# SpeedOfLightController.net
KiCad netlist of a schematic drawn in EAGLE
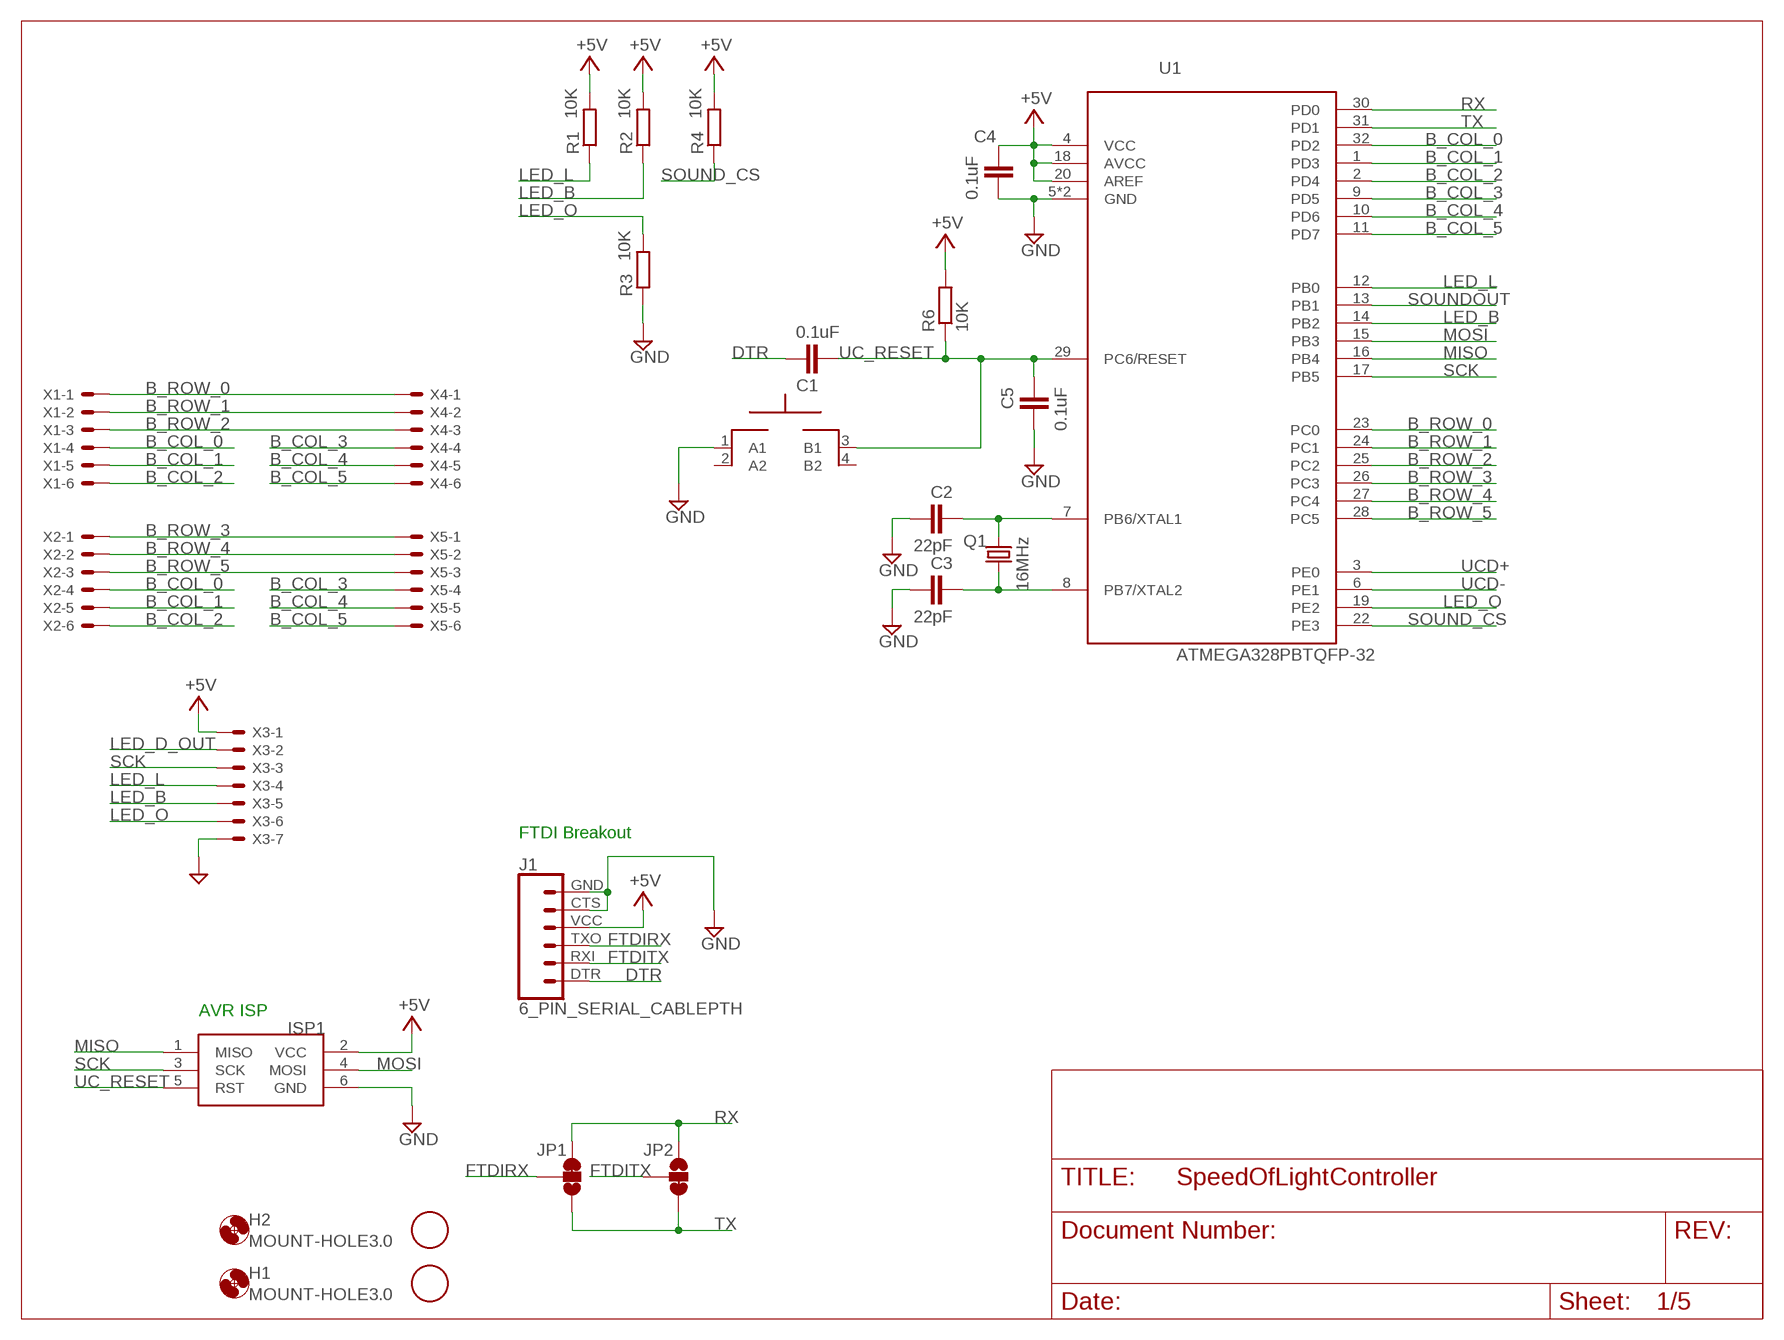
[diagram p0: schematic, sheet 1]
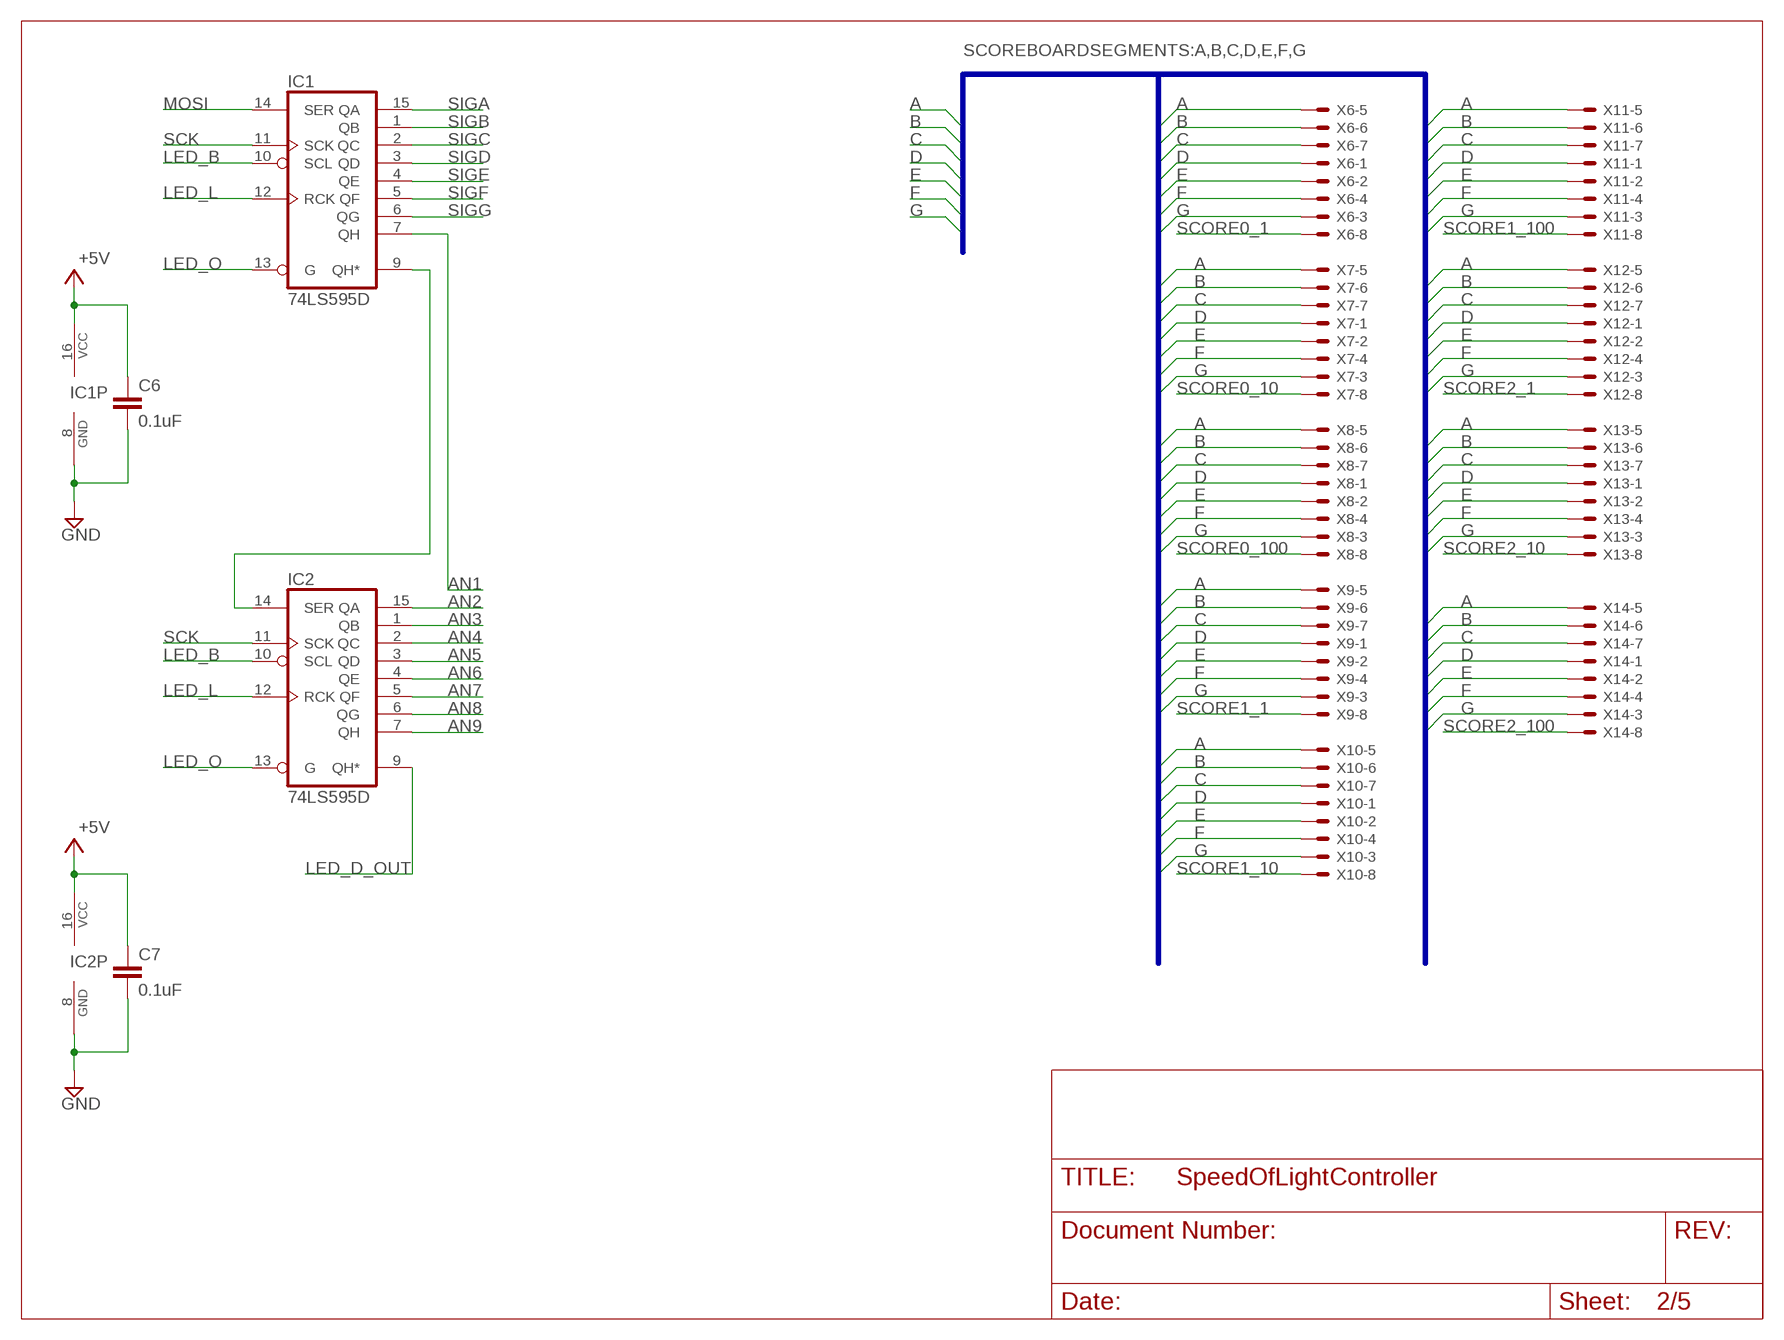
[diagram p1: schematic, sheet 2]
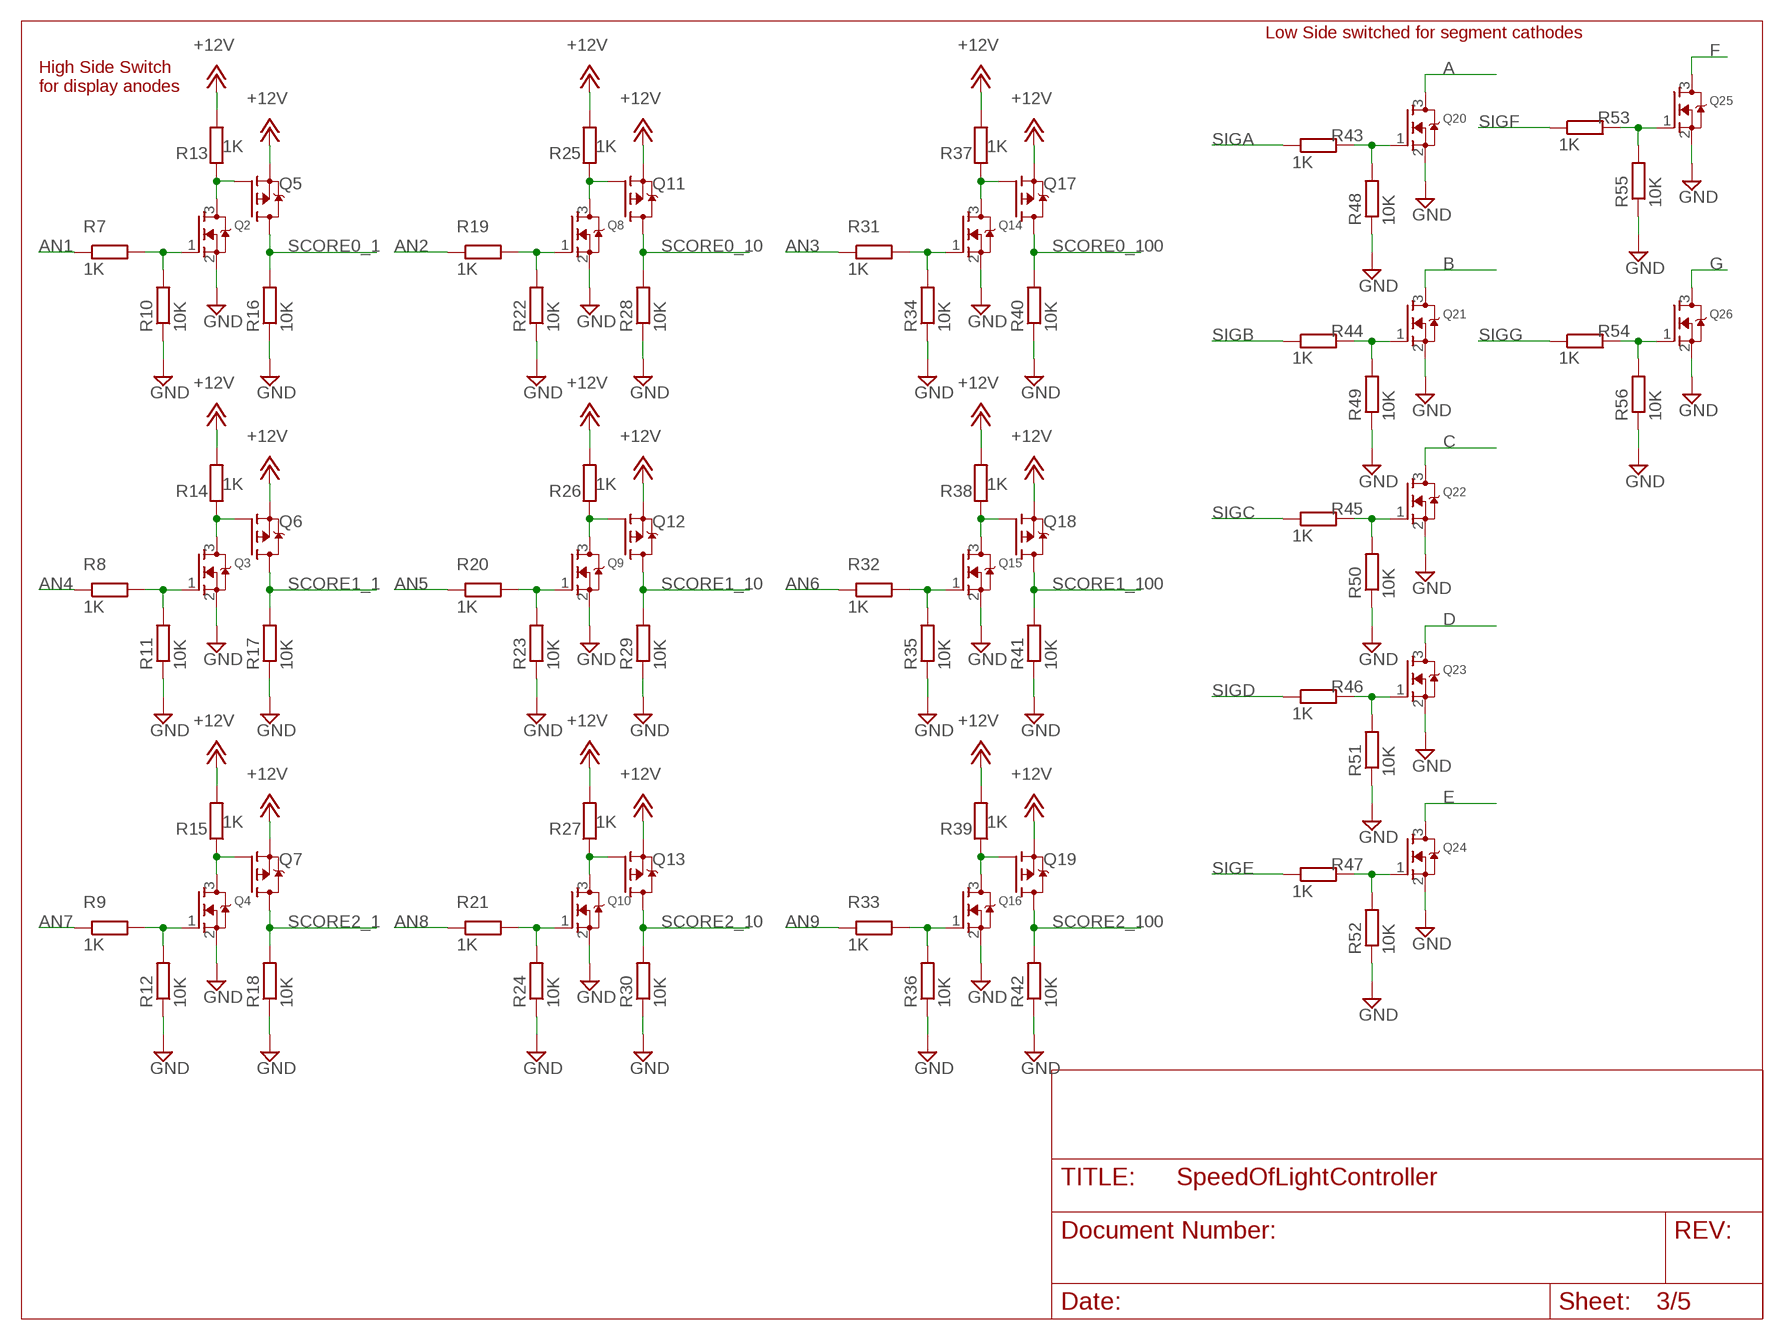
[diagram p2: schematic, sheet 3]
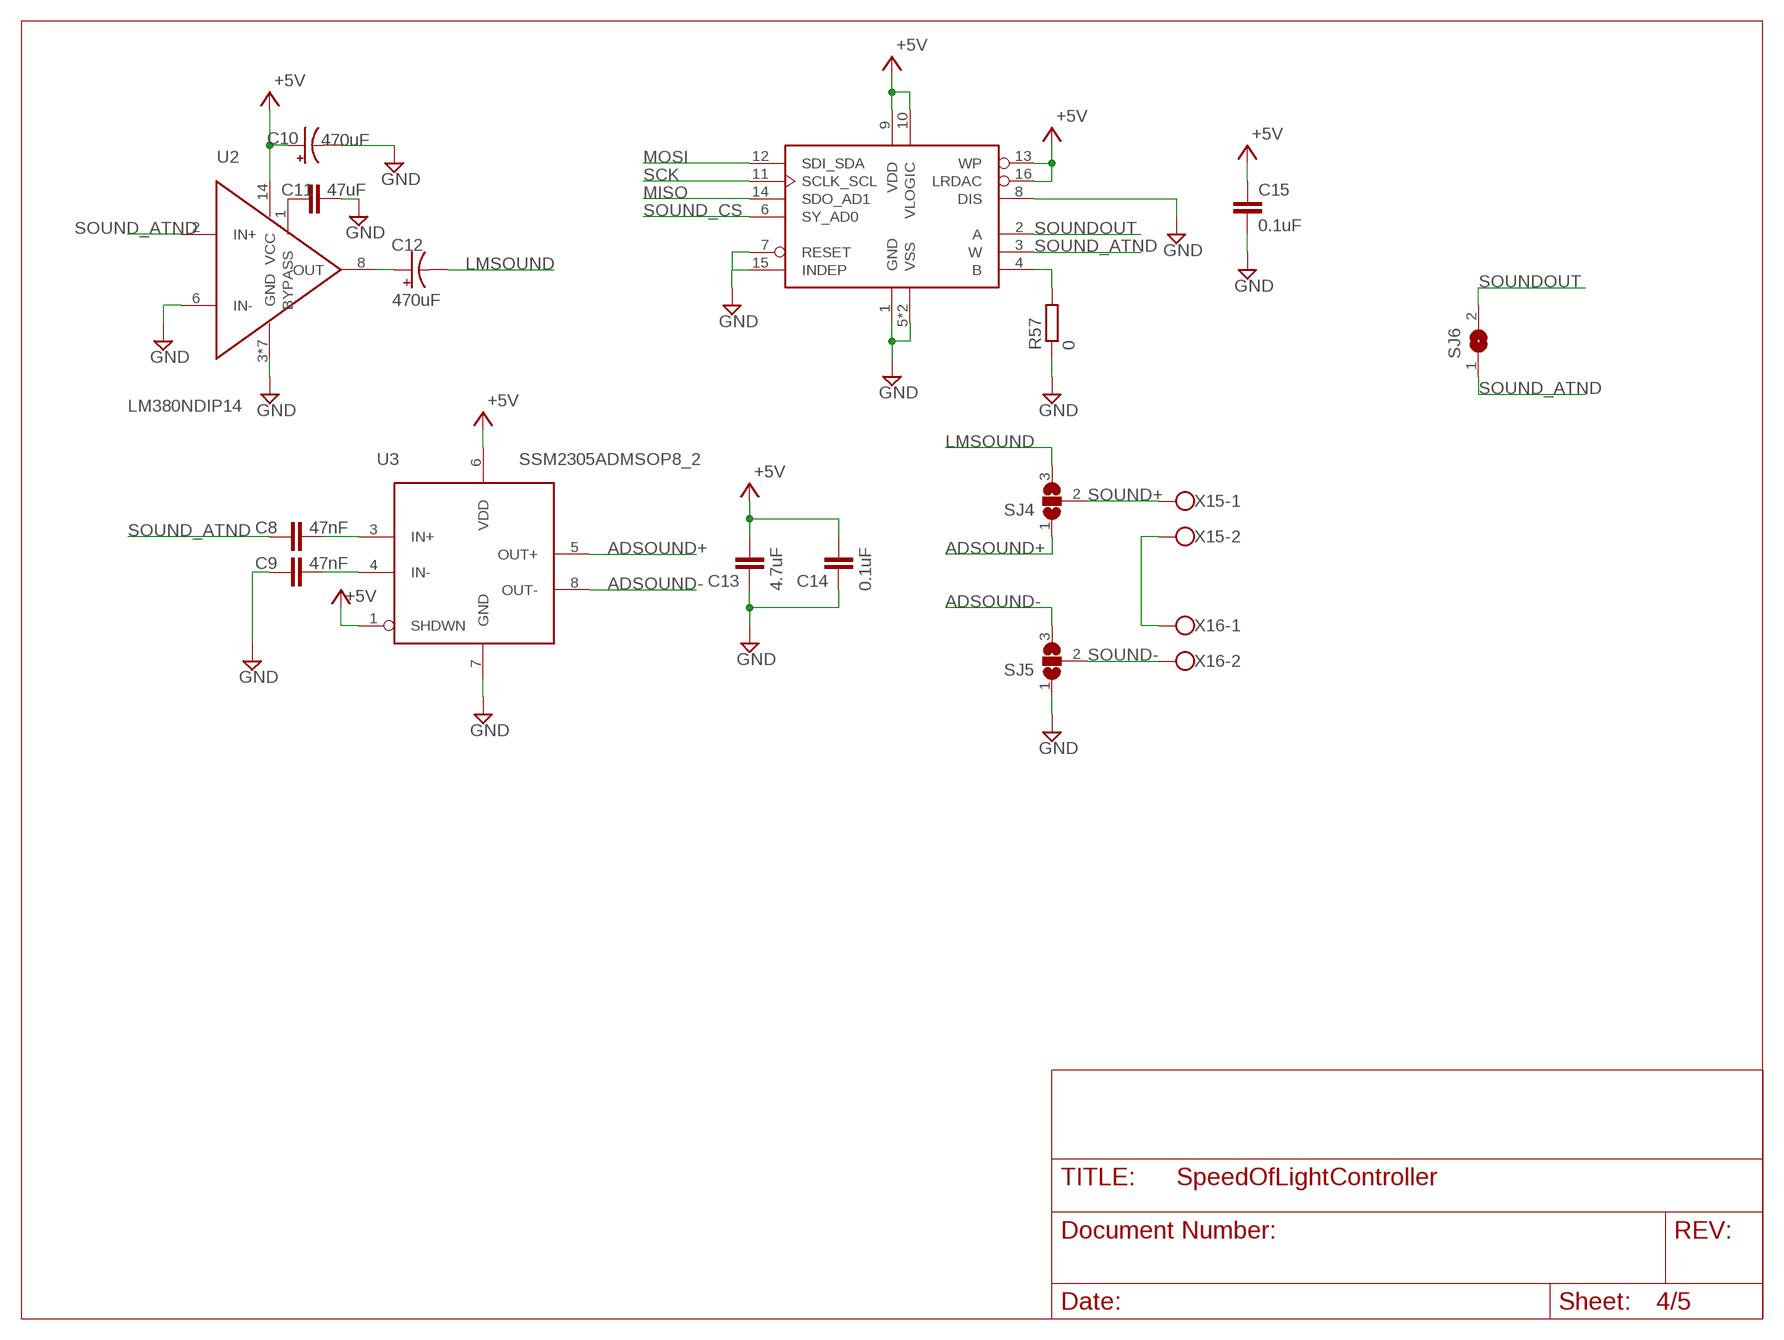
[diagram p3: schematic, sheet 4]
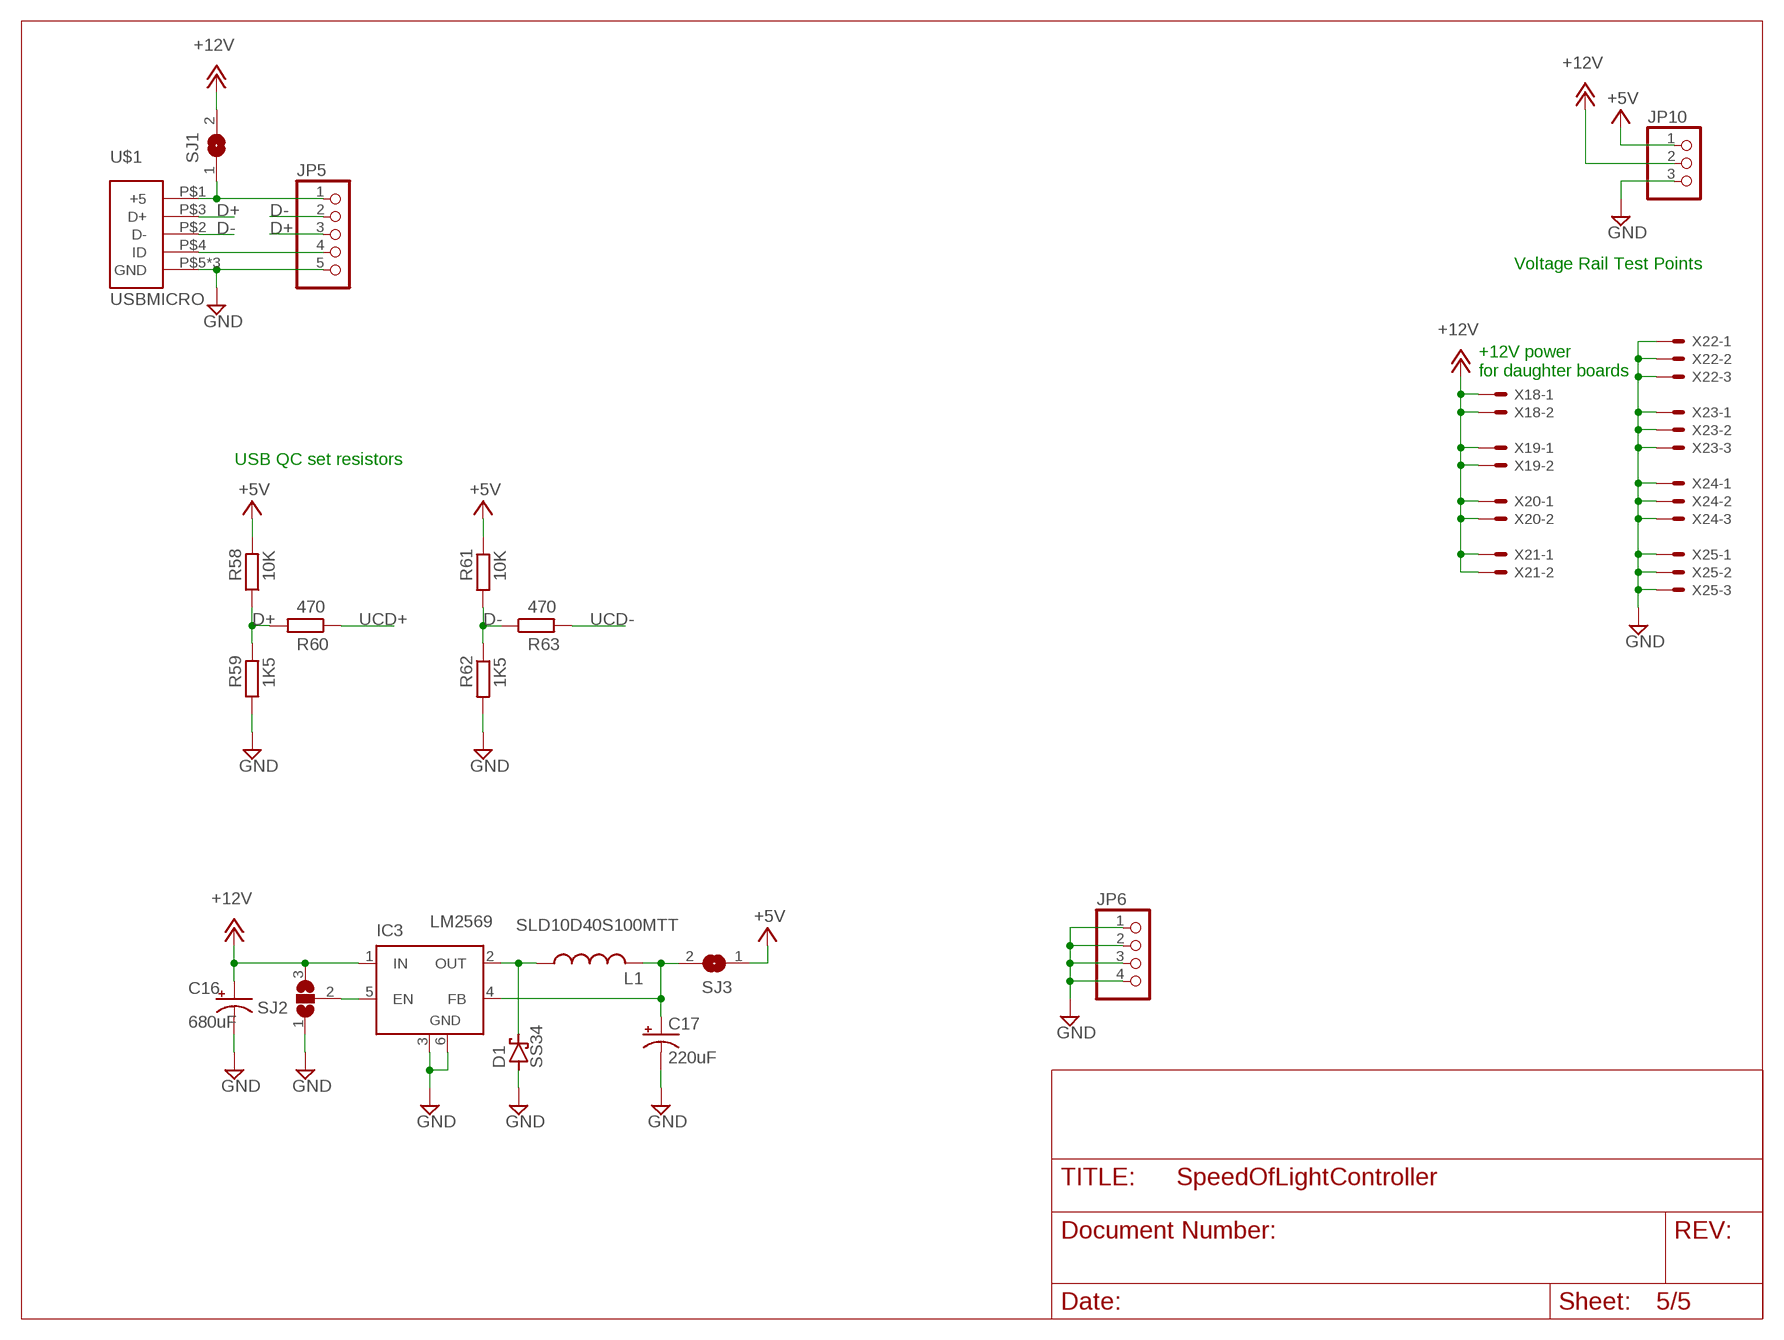
[diagram p4: schematic, sheet 5]

(export (version "E")
  (design (tool "Eeschema 10.0.6"))
  (components
    (comp (ref "C6")
      (value "0.1uF")
      (footprint "eagle-import:C0805")
      (libsource (lib "eagle-import") (part "C-EUC0805"))
    )
    (comp (ref "C7")
      (value "0.1uF")
      (footprint "eagle-import:C0805")
      (libsource (lib "eagle-import") (part "C-EUC0805"))
    )
    (comp (ref "IC1")
      (value "74LS595D")
      (footprint "eagle-import:SO16")
      (libsource (lib "eagle-import") (part "74595DLS"))
    )
    (comp (ref "IC2")
      (value "74LS595D")
      (footprint "eagle-import:SO16")
      (libsource (lib "eagle-import") (part "74595DLS"))
    )
    (comp (ref "X6")
      (value "JST-XH-08-PIN-LONG-PAD")
      (footprint "eagle-import:JST-XH-08-PACKAGE-LONG-PAD")
      (libsource (lib "eagle-import") (part "JST-XH-08-PIN-LONG-PAD"))
    )
    (comp (ref "X7")
      (value "JST-XH-08-PIN-LONG-PAD")
      (footprint "eagle-import:JST-XH-08-PACKAGE-LONG-PAD")
      (libsource (lib "eagle-import") (part "JST-XH-08-PIN-LONG-PAD"))
    )
    (comp (ref "X8")
      (value "JST-XH-08-PIN-LONG-PAD")
      (footprint "eagle-import:JST-XH-08-PACKAGE-LONG-PAD")
      (libsource (lib "eagle-import") (part "JST-XH-08-PIN-LONG-PAD"))
    )
    (comp (ref "X9")
      (value "JST-XH-08-PIN-LONG-PAD")
      (footprint "eagle-import:JST-XH-08-PACKAGE-LONG-PAD")
      (libsource (lib "eagle-import") (part "JST-XH-08-PIN-LONG-PAD"))
    )
    (comp (ref "X10")
      (value "JST-XH-08-PIN-LONG-PAD")
      (footprint "eagle-import:JST-XH-08-PACKAGE-LONG-PAD")
      (libsource (lib "eagle-import") (part "JST-XH-08-PIN-LONG-PAD"))
    )
    (comp (ref "X11")
      (value "JST-XH-08-PIN-LONG-PAD")
      (footprint "eagle-import:JST-XH-08-PACKAGE-LONG-PAD")
      (libsource (lib "eagle-import") (part "JST-XH-08-PIN-LONG-PAD"))
    )
    (comp (ref "X12")
      (value "JST-XH-08-PIN-LONG-PAD")
      (footprint "eagle-import:JST-XH-08-PACKAGE-LONG-PAD")
      (libsource (lib "eagle-import") (part "JST-XH-08-PIN-LONG-PAD"))
    )
    (comp (ref "X13")
      (value "JST-XH-08-PIN-LONG-PAD")
      (footprint "eagle-import:JST-XH-08-PACKAGE-LONG-PAD")
      (libsource (lib "eagle-import") (part "JST-XH-08-PIN-LONG-PAD"))
    )
    (comp (ref "X14")
      (value "JST-XH-08-PIN-LONG-PAD")
      (footprint "eagle-import:JST-XH-08-PACKAGE-LONG-PAD")
      (libsource (lib "eagle-import") (part "JST-XH-08-PIN-LONG-PAD"))
    )
    (comp (ref "C16")
      (value "680uF")
      (footprint "eagle-import:140CLH-0810")
      (libsource (lib "eagle-import") (part "CPOL-US140CLH-0810"))
    )
    (comp (ref "C17")
      (value "220uF")
      (footprint "eagle-import:140CLH-0810")
      (libsource (lib "eagle-import") (part "CPOL-US140CLH-0810"))
    )
    (comp (ref "D1")
      (value "SS34")
      (footprint "eagle-import:SMA")
      (libsource (lib "eagle-import") (part "SS34"))
    )
    (comp (ref "IC3")
      (value "LM2596S")
      (footprint "eagle-import:TO263-5")
      (libsource (lib "eagle-import") (part "LM2596S"))
    )
    (comp (ref "JP5")
      (value "PINHD-1X5")
      (footprint "eagle-import:1X05")
      (libsource (lib "eagle-import") (part "PINHD-1X5"))
    )
    (comp (ref "JP6")
      (value "PINHD-1X4")
      (footprint "eagle-import:1X04")
      (libsource (lib "eagle-import") (part "PINHD-1X4"))
    )
    (comp (ref "JP10")
      (value "PINHD-1X3")
      (footprint "eagle-import:1X03")
      (libsource (lib "eagle-import") (part "PINHD-1X3"))
    )
    (comp (ref "L1")
      (value "SLD10D40S100MTT")
      (footprint "eagle-import:SMD10.5X10.3")
      (libsource (lib "eagle-import") (part "SLD10D40S100MTT"))
    )
    (comp (ref "R58")
      (value "10K")
      (footprint "eagle-import:R0805")
      (libsource (lib "eagle-import") (part "R-EU_R0805"))
    )
    (comp (ref "R59")
      (value "1K5")
      (footprint "eagle-import:R0805")
      (libsource (lib "eagle-import") (part "R-EU_R0805"))
    )
    (comp (ref "R60")
      (value "470")
      (footprint "eagle-import:R0805")
      (libsource (lib "eagle-import") (part "R-EU_R0805"))
    )
    (comp (ref "R61")
      (value "10K")
      (footprint "eagle-import:R0805")
      (libsource (lib "eagle-import") (part "R-EU_R0805"))
    )
    (comp (ref "R62")
      (value "1K5")
      (footprint "eagle-import:R0805")
      (libsource (lib "eagle-import") (part "R-EU_R0805"))
    )
    (comp (ref "R63")
      (value "470")
      (footprint "eagle-import:R0805")
      (libsource (lib "eagle-import") (part "R-EU_R0805"))
    )
    (comp (ref "SJ1") (value "SJ") (footprint "eagle-import:SJ") (libsource (lib "eagle-import") (part "SJ")))
    (comp (ref "SJ2")
      (value "SJ2WW")
      (footprint "eagle-import:SJ_2W")
      (libsource (lib "eagle-import") (part "SJ2WW"))
    )
    (comp (ref "SJ3") (value "SJ") (footprint "eagle-import:SJ") (libsource (lib "eagle-import") (part "SJ")))
    (comp (ref "U$1")
      (value "USBMICRO")
      (footprint "eagle-import:USBMICRO")
      (libsource (lib "eagle-import") (part "USBMICRO"))
    )
    (comp (ref "X18")
      (value "JST-XH-02-PIN-LONG-PAD")
      (footprint "eagle-import:JST-XH-02-PACKAGE-LONG-PAD")
      (libsource (lib "eagle-import") (part "JST-XH-02-PIN-LONG-PAD"))
    )
    (comp (ref "X19")
      (value "JST-XH-02-PIN-LONG-PAD")
      (footprint "eagle-import:JST-XH-02-PACKAGE-LONG-PAD")
      (libsource (lib "eagle-import") (part "JST-XH-02-PIN-LONG-PAD"))
    )
    (comp (ref "X20")
      (value "JST-XH-02-PIN-LONG-PAD")
      (footprint "eagle-import:JST-XH-02-PACKAGE-LONG-PAD")
      (libsource (lib "eagle-import") (part "JST-XH-02-PIN-LONG-PAD"))
    )
    (comp (ref "X21")
      (value "JST-XH-02-PIN-LONG-PAD")
      (footprint "eagle-import:JST-XH-02-PACKAGE-LONG-PAD")
      (libsource (lib "eagle-import") (part "JST-XH-02-PIN-LONG-PAD"))
    )
    (comp (ref "X22")
      (value "JST-XH-03-PIN-LONG-PAD")
      (footprint "eagle-import:JST-XH-03-PACKAGE-LONG-PAD")
      (libsource (lib "eagle-import") (part "JST-XH-03-PIN-LONG-PAD"))
    )
    (comp (ref "X23")
      (value "JST-XH-03-PIN-LONG-PAD")
      (footprint "eagle-import:JST-XH-03-PACKAGE-LONG-PAD")
      (libsource (lib "eagle-import") (part "JST-XH-03-PIN-LONG-PAD"))
    )
    (comp (ref "X24")
      (value "JST-XH-03-PIN-LONG-PAD")
      (footprint "eagle-import:JST-XH-03-PACKAGE-LONG-PAD")
      (libsource (lib "eagle-import") (part "JST-XH-03-PIN-LONG-PAD"))
    )
    (comp (ref "X25")
      (value "JST-XH-03-PIN-LONG-PAD")
      (footprint "eagle-import:JST-XH-03-PACKAGE-LONG-PAD")
      (libsource (lib "eagle-import") (part "JST-XH-03-PIN-LONG-PAD"))
    )
    (comp (ref "C1")
      (value "0.1uF")
      (footprint "eagle-import:C0805")
      (libsource (lib "eagle-import") (part "C-EUC0805"))
    )
    (comp (ref "C2")
      (value "22pF")
      (footprint "eagle-import:C0805")
      (libsource (lib "eagle-import") (part "C-EUC0805"))
    )
    (comp (ref "C3")
      (value "22pF")
      (footprint "eagle-import:C0805")
      (libsource (lib "eagle-import") (part "C-EUC0805"))
    )
    (comp (ref "C4")
      (value "0.1uF")
      (footprint "eagle-import:C0805")
      (libsource (lib "eagle-import") (part "C-EUC0805"))
    )
    (comp (ref "C5")
      (value "0.1uF")
      (footprint "eagle-import:C0805")
      (libsource (lib "eagle-import") (part "C-EUC0805"))
    )
    (comp (ref "F1")
      (value "FIDUCIAL")
      (footprint "eagle-import:FIDUCIAL_1MM")
      (libsource (lib "eagle-import") (part "FIDUCIAL"))
    )
    (comp (ref "F2")
      (value "FIDUCIAL")
      (footprint "eagle-import:FIDUCIAL_1MM")
      (libsource (lib "eagle-import") (part "FIDUCIAL"))
    )
    (comp (ref "H1")
      (value "MOUNT-HOLE3.0")
      (footprint "eagle-import:3,0")
      (libsource (lib "eagle-import") (part "MOUNT-HOLE3.0"))
    )
    (comp (ref "H2")
      (value "MOUNT-HOLE3.0")
      (footprint "eagle-import:3,0")
      (libsource (lib "eagle-import") (part "MOUNT-HOLE3.0"))
    )
    (comp (ref "ISP1")
      (value "AVRISP-6")
      (footprint "eagle-import:AVRISP")
      (libsource (lib "eagle-import") (part "AVRISP-6"))
    )
    (comp (ref "J1")
      (value "6_PIN_SERIAL_CABLEPTH")
      (footprint "eagle-import:FTDI_BASIC")
      (libsource (lib "eagle-import") (part "6_PIN_SERIAL_CABLEPTH"))
    )
    (comp (ref "JP1")
      (value "JUMPER-SMT_3_1-NC_TRACE_SILK")
      (footprint "eagle-import:SMT-JUMPER_3_1-NC_TRACE_SILK")
      (libsource (lib "eagle-import") (part "JUMPER-SMT_3_1-NC_TRACE_SILK"))
    )
    (comp (ref "JP2")
      (value "JUMPER-SMT_3_1-NC_TRACE_SILK")
      (footprint "eagle-import:SMT-JUMPER_3_1-NC_TRACE_SILK")
      (libsource (lib "eagle-import") (part "JUMPER-SMT_3_1-NC_TRACE_SILK"))
    )
    (comp (ref "Q1")
      (value "16MHz")
      (footprint "eagle-import:HC49UP")
      (libsource (lib "eagle-import") (part "CRYSTALHC49UP"))
    )
    (comp (ref "R1")
      (value "10K")
      (footprint "eagle-import:R0805")
      (libsource (lib "eagle-import") (part "R-EU_R0805"))
    )
    (comp (ref "R2")
      (value "10K")
      (footprint "eagle-import:R0805")
      (libsource (lib "eagle-import") (part "R-EU_R0805"))
    )
    (comp (ref "R3")
      (value "10K")
      (footprint "eagle-import:R0805")
      (libsource (lib "eagle-import") (part "R-EU_R0805"))
    )
    (comp (ref "R4")
      (value "10K")
      (footprint "eagle-import:R0805")
      (libsource (lib "eagle-import") (part "R-EU_R0805"))
    )
    (comp (ref "R6")
      (value "10K")
      (footprint "eagle-import:R0805")
      (libsource (lib "eagle-import") (part "R-EU_R0805"))
    )
    (comp (ref "SW1")
      (value "MOMENTARYBUTTON")
      (footprint "eagle-import:SPST_NO_SMD")
      (libsource (lib "eagle-import") (part "MOMENTARYBUTTON"))
    )
    (comp (ref "U1")
      (value "ATMEGA328PBTQFP-32")
      (footprint "eagle-import:QFP80P900X900X120-32N")
      (libsource (lib "eagle-import") (part "ATMEGA328PBTQFP-32"))
    )
    (comp (ref "X1")
      (value "JST-XH-06-PIN-LONG-PAD")
      (footprint "eagle-import:JST-XH-06-PACKAGE-LONG-PAD")
      (libsource (lib "eagle-import") (part "JST-XH-06-PIN-LONG-PAD"))
    )
    (comp (ref "X2")
      (value "JST-XH-06-PIN-LONG-PAD")
      (footprint "eagle-import:JST-XH-06-PACKAGE-LONG-PAD")
      (libsource (lib "eagle-import") (part "JST-XH-06-PIN-LONG-PAD"))
    )
    (comp (ref "X3")
      (value "JST-XH-07-PIN-LONG-PAD")
      (footprint "eagle-import:JST-XH-07-PACKAGE-LONG-PAD")
      (libsource (lib "eagle-import") (part "JST-XH-07-PIN-LONG-PAD"))
    )
    (comp (ref "X4")
      (value "JST-XH-06-PIN-LONG-PAD")
      (footprint "eagle-import:JST-XH-06-PACKAGE-LONG-PAD")
      (libsource (lib "eagle-import") (part "JST-XH-06-PIN-LONG-PAD"))
    )
    (comp (ref "X5")
      (value "JST-XH-06-PIN-LONG-PAD")
      (footprint "eagle-import:JST-XH-06-PACKAGE-LONG-PAD")
      (libsource (lib "eagle-import") (part "JST-XH-06-PIN-LONG-PAD"))
    )
    (comp (ref "C8")
      (value "47nF")
      (footprint "eagle-import:C0805")
      (libsource (lib "eagle-import") (part "C-EUC0805"))
    )
    (comp (ref "C9")
      (value "47nF")
      (footprint "eagle-import:C0805")
      (libsource (lib "eagle-import") (part "C-EUC0805"))
    )
    (comp (ref "C10")
      (value "470uF")
      (footprint "eagle-import:140CLH-0810")
      (libsource (lib "eagle-import") (part "CPOL-US140CLH-0810"))
    )
    (comp (ref "C11")
      (value "47uF")
      (footprint "eagle-import:C0805")
      (libsource (lib "eagle-import") (part "C-EUC0805"))
    )
    (comp (ref "C12")
      (value "470uF")
      (footprint "eagle-import:140CLH-0810")
      (libsource (lib "eagle-import") (part "CPOL-US140CLH-0810"))
    )
    (comp (ref "C13")
      (value "4.7uF")
      (footprint "eagle-import:C0805")
      (libsource (lib "eagle-import") (part "C-EUC0805"))
    )
    (comp (ref "C14")
      (value "0.1uF")
      (footprint "eagle-import:C0805")
      (libsource (lib "eagle-import") (part "C-EUC0805"))
    )
    (comp (ref "C15")
      (value "0.1uF")
      (footprint "eagle-import:C0805")
      (libsource (lib "eagle-import") (part "C-EUC0805"))
    )
    (comp (ref "R57")
      (value "0")
      (footprint "eagle-import:R0805W")
      (libsource (lib "eagle-import") (part "R-EU_R0805W"))
    )
    (comp (ref "SJ4")
      (value "SJ2WW")
      (footprint "eagle-import:SJ_2W")
      (libsource (lib "eagle-import") (part "SJ2WW"))
    )
    (comp (ref "SJ5")
      (value "SJ2WW")
      (footprint "eagle-import:SJ_2W")
      (libsource (lib "eagle-import") (part "SJ2WW"))
    )
    (comp (ref "SJ6") (value "SJ") (footprint "eagle-import:SJ") (libsource (lib "eagle-import") (part "SJ")))
    (comp (ref "U2")
      (value "LM380NDIP14")
      (footprint "eagle-import:DIP762W53P254L1969H508Q14B")
      (libsource (lib "eagle-import") (part "LM380NDIP14"))
    )
    (comp (ref "U3")
      (value "SSM2305ADMSOP8_2")
      (footprint "eagle-import:SOP65P490X95-8N")
      (libsource (lib "eagle-import") (part "SSM2305ADMSOP8_2"))
    )
    (comp (ref "U4")
      (value "AD5141ADLFCSP3")
      (footprint "eagle-import:QFN50P300X300X80-17T160N")
      (libsource (lib "eagle-import") (part "AD5141ADLFCSP3"))
    )
    (comp (ref "X15")
      (value "1X02_5MM_SCREW")
      (footprint "eagle-import:W237-102")
      (fields (field (name "MPN") "237-102"))
      (libsource (lib "eagle-import") (part "1X02_5MM_SCREW"))
    )
    (comp (ref "X16")
      (value "1X02_5MM_SCREW")
      (footprint "eagle-import:W237-102")
      (fields (field (name "MPN") "237-102"))
      (libsource (lib "eagle-import") (part "1X02_5MM_SCREW"))
    )
    (comp (ref "Q2")
      (value "AO3414SOT23")
      (footprint "eagle-import:SOT95P240X110-3N")
      (libsource (lib "eagle-import") (part "AO3414SOT23"))
    )
    (comp (ref "Q3")
      (value "AO3414SOT23")
      (footprint "eagle-import:SOT95P240X110-3N")
      (libsource (lib "eagle-import") (part "AO3414SOT23"))
    )
    (comp (ref "Q4")
      (value "AO3414SOT23")
      (footprint "eagle-import:SOT95P240X110-3N")
      (libsource (lib "eagle-import") (part "AO3414SOT23"))
    )
    (comp (ref "Q5")
      (value "AO3415")
      (footprint "eagle-import:SOT95P240X110-3N")
      (libsource (lib "eagle-import") (part "AO3415"))
    )
    (comp (ref "Q6")
      (value "AO3415")
      (footprint "eagle-import:SOT95P240X110-3N")
      (libsource (lib "eagle-import") (part "AO3415"))
    )
    (comp (ref "Q7")
      (value "AO3415")
      (footprint "eagle-import:SOT95P240X110-3N")
      (libsource (lib "eagle-import") (part "AO3415"))
    )
    (comp (ref "Q8")
      (value "AO3414SOT23")
      (footprint "eagle-import:SOT95P240X110-3N")
      (libsource (lib "eagle-import") (part "AO3414SOT23"))
    )
    (comp (ref "Q9")
      (value "AO3414SOT23")
      (footprint "eagle-import:SOT95P240X110-3N")
      (libsource (lib "eagle-import") (part "AO3414SOT23"))
    )
    (comp (ref "Q10")
      (value "AO3414SOT23")
      (footprint "eagle-import:SOT95P240X110-3N")
      (libsource (lib "eagle-import") (part "AO3414SOT23"))
    )
    (comp (ref "Q11")
      (value "AO3415")
      (footprint "eagle-import:SOT95P240X110-3N")
      (libsource (lib "eagle-import") (part "AO3415"))
    )
    (comp (ref "Q12")
      (value "AO3415")
      (footprint "eagle-import:SOT95P240X110-3N")
      (libsource (lib "eagle-import") (part "AO3415"))
    )
    (comp (ref "Q13")
      (value "AO3415")
      (footprint "eagle-import:SOT95P240X110-3N")
      (libsource (lib "eagle-import") (part "AO3415"))
    )
    (comp (ref "Q14")
      (value "AO3414SOT23")
      (footprint "eagle-import:SOT95P240X110-3N")
      (libsource (lib "eagle-import") (part "AO3414SOT23"))
    )
    (comp (ref "Q15")
      (value "AO3414SOT23")
      (footprint "eagle-import:SOT95P240X110-3N")
      (libsource (lib "eagle-import") (part "AO3414SOT23"))
    )
    (comp (ref "Q16")
      (value "AO3414SOT23")
      (footprint "eagle-import:SOT95P240X110-3N")
      (libsource (lib "eagle-import") (part "AO3414SOT23"))
    )
    (comp (ref "Q17")
      (value "AO3415")
      (footprint "eagle-import:SOT95P240X110-3N")
      (libsource (lib "eagle-import") (part "AO3415"))
    )
    (comp (ref "Q18")
      (value "AO3415")
      (footprint "eagle-import:SOT95P240X110-3N")
      (libsource (lib "eagle-import") (part "AO3415"))
    )
    (comp (ref "Q19")
      (value "AO3415")
      (footprint "eagle-import:SOT95P240X110-3N")
      (libsource (lib "eagle-import") (part "AO3415"))
    )
    (comp (ref "Q20")
      (value "AO3414SOT23")
      (footprint "eagle-import:SOT95P240X110-3N")
      (libsource (lib "eagle-import") (part "AO3414SOT23"))
    )
    (comp (ref "Q21")
      (value "AO3414SOT23")
      (footprint "eagle-import:SOT95P240X110-3N")
      (libsource (lib "eagle-import") (part "AO3414SOT23"))
    )
    (comp (ref "Q22")
      (value "AO3414SOT23")
      (footprint "eagle-import:SOT95P240X110-3N")
      (libsource (lib "eagle-import") (part "AO3414SOT23"))
    )
    (comp (ref "Q23")
      (value "AO3414SOT23")
      (footprint "eagle-import:SOT95P240X110-3N")
      (libsource (lib "eagle-import") (part "AO3414SOT23"))
    )
    (comp (ref "Q24")
      (value "AO3414SOT23")
      (footprint "eagle-import:SOT95P240X110-3N")
      (libsource (lib "eagle-import") (part "AO3414SOT23"))
    )
    (comp (ref "Q25")
      (value "AO3414SOT23")
      (footprint "eagle-import:SOT95P240X110-3N")
      (libsource (lib "eagle-import") (part "AO3414SOT23"))
    )
    (comp (ref "Q26")
      (value "AO3414SOT23")
      (footprint "eagle-import:SOT95P240X110-3N")
      (libsource (lib "eagle-import") (part "AO3414SOT23"))
    )
    (comp (ref "R7")
      (value "1K")
      (footprint "eagle-import:R0805")
      (libsource (lib "eagle-import") (part "R-EU_R0805"))
    )
    (comp (ref "R8")
      (value "1K")
      (footprint "eagle-import:R0805")
      (libsource (lib "eagle-import") (part "R-EU_R0805"))
    )
    (comp (ref "R9")
      (value "1K")
      (footprint "eagle-import:R0805")
      (libsource (lib "eagle-import") (part "R-EU_R0805"))
    )
    (comp (ref "R10")
      (value "10K")
      (footprint "eagle-import:R0805")
      (libsource (lib "eagle-import") (part "R-EU_R0805"))
    )
    (comp (ref "R11")
      (value "10K")
      (footprint "eagle-import:R0805")
      (libsource (lib "eagle-import") (part "R-EU_R0805"))
    )
    (comp (ref "R12")
      (value "10K")
      (footprint "eagle-import:R0805")
      (libsource (lib "eagle-import") (part "R-EU_R0805"))
    )
    (comp (ref "R13")
      (value "1K")
      (footprint "eagle-import:R0805")
      (libsource (lib "eagle-import") (part "R-EU_R0805"))
    )
    (comp (ref "R14")
      (value "1K")
      (footprint "eagle-import:R0805")
      (libsource (lib "eagle-import") (part "R-EU_R0805"))
    )
    (comp (ref "R15")
      (value "1K")
      (footprint "eagle-import:R0805")
      (libsource (lib "eagle-import") (part "R-EU_R0805"))
    )
    (comp (ref "R16")
      (value "10K")
      (footprint "eagle-import:R0805")
      (libsource (lib "eagle-import") (part "R-EU_R0805"))
    )
    (comp (ref "R17")
      (value "10K")
      (footprint "eagle-import:R0805")
      (libsource (lib "eagle-import") (part "R-EU_R0805"))
    )
    (comp (ref "R18")
      (value "10K")
      (footprint "eagle-import:R0805")
      (libsource (lib "eagle-import") (part "R-EU_R0805"))
    )
    (comp (ref "R19")
      (value "1K")
      (footprint "eagle-import:R0805")
      (libsource (lib "eagle-import") (part "R-EU_R0805"))
    )
    (comp (ref "R20")
      (value "1K")
      (footprint "eagle-import:R0805")
      (libsource (lib "eagle-import") (part "R-EU_R0805"))
    )
    (comp (ref "R21")
      (value "1K")
      (footprint "eagle-import:R0805")
      (libsource (lib "eagle-import") (part "R-EU_R0805"))
    )
    (comp (ref "R22")
      (value "10K")
      (footprint "eagle-import:R0805")
      (libsource (lib "eagle-import") (part "R-EU_R0805"))
    )
    (comp (ref "R23")
      (value "10K")
      (footprint "eagle-import:R0805")
      (libsource (lib "eagle-import") (part "R-EU_R0805"))
    )
    (comp (ref "R24")
      (value "10K")
      (footprint "eagle-import:R0805")
      (libsource (lib "eagle-import") (part "R-EU_R0805"))
    )
    (comp (ref "R25")
      (value "1K")
      (footprint "eagle-import:R0805")
      (libsource (lib "eagle-import") (part "R-EU_R0805"))
    )
    (comp (ref "R26")
      (value "1K")
      (footprint "eagle-import:R0805")
      (libsource (lib "eagle-import") (part "R-EU_R0805"))
    )
    (comp (ref "R27")
      (value "1K")
      (footprint "eagle-import:R0805")
      (libsource (lib "eagle-import") (part "R-EU_R0805"))
    )
    (comp (ref "R28")
      (value "10K")
      (footprint "eagle-import:R0805")
      (libsource (lib "eagle-import") (part "R-EU_R0805"))
    )
    (comp (ref "R29")
      (value "10K")
      (footprint "eagle-import:R0805")
      (libsource (lib "eagle-import") (part "R-EU_R0805"))
    )
    (comp (ref "R30")
      (value "10K")
      (footprint "eagle-import:R0805")
      (libsource (lib "eagle-import") (part "R-EU_R0805"))
    )
    (comp (ref "R31")
      (value "1K")
      (footprint "eagle-import:R0805")
      (libsource (lib "eagle-import") (part "R-EU_R0805"))
    )
    (comp (ref "R32")
      (value "1K")
      (footprint "eagle-import:R0805")
      (libsource (lib "eagle-import") (part "R-EU_R0805"))
    )
    (comp (ref "R33")
      (value "1K")
      (footprint "eagle-import:R0805")
      (libsource (lib "eagle-import") (part "R-EU_R0805"))
    )
    (comp (ref "R34")
      (value "10K")
      (footprint "eagle-import:R0805")
      (libsource (lib "eagle-import") (part "R-EU_R0805"))
    )
    (comp (ref "R35")
      (value "10K")
      (footprint "eagle-import:R0805")
      (libsource (lib "eagle-import") (part "R-EU_R0805"))
    )
    (comp (ref "R36")
      (value "10K")
      (footprint "eagle-import:R0805")
      (libsource (lib "eagle-import") (part "R-EU_R0805"))
    )
    (comp (ref "R37")
      (value "1K")
      (footprint "eagle-import:R0805")
      (libsource (lib "eagle-import") (part "R-EU_R0805"))
    )
    (comp (ref "R38")
      (value "1K")
      (footprint "eagle-import:R0805")
      (libsource (lib "eagle-import") (part "R-EU_R0805"))
    )
    (comp (ref "R39")
      (value "1K")
      (footprint "eagle-import:R0805")
      (libsource (lib "eagle-import") (part "R-EU_R0805"))
    )
    (comp (ref "R40")
      (value "10K")
      (footprint "eagle-import:R0805")
      (libsource (lib "eagle-import") (part "R-EU_R0805"))
    )
    (comp (ref "R41")
      (value "10K")
      (footprint "eagle-import:R0805")
      (libsource (lib "eagle-import") (part "R-EU_R0805"))
    )
    (comp (ref "R42")
      (value "10K")
      (footprint "eagle-import:R0805")
      (libsource (lib "eagle-import") (part "R-EU_R0805"))
    )
    (comp (ref "R43")
      (value "1K")
      (footprint "eagle-import:R0805")
      (libsource (lib "eagle-import") (part "R-EU_R0805"))
    )
    (comp (ref "R44")
      (value "1K")
      (footprint "eagle-import:R0805")
      (libsource (lib "eagle-import") (part "R-EU_R0805"))
    )
    (comp (ref "R45")
      (value "1K")
      (footprint "eagle-import:R0805")
      (libsource (lib "eagle-import") (part "R-EU_R0805"))
    )
    (comp (ref "R46")
      (value "1K")
      (footprint "eagle-import:R0805")
      (libsource (lib "eagle-import") (part "R-EU_R0805"))
    )
    (comp (ref "R47")
      (value "1K")
      (footprint "eagle-import:R0805")
      (libsource (lib "eagle-import") (part "R-EU_R0805"))
    )
    (comp (ref "R48")
      (value "10K")
      (footprint "eagle-import:R0805")
      (libsource (lib "eagle-import") (part "R-EU_R0805"))
    )
    (comp (ref "R49")
      (value "10K")
      (footprint "eagle-import:R0805")
      (libsource (lib "eagle-import") (part "R-EU_R0805"))
    )
    (comp (ref "R50")
      (value "10K")
      (footprint "eagle-import:R0805")
      (libsource (lib "eagle-import") (part "R-EU_R0805"))
    )
    (comp (ref "R51")
      (value "10K")
      (footprint "eagle-import:R0805")
      (libsource (lib "eagle-import") (part "R-EU_R0805"))
    )
    (comp (ref "R52")
      (value "10K")
      (footprint "eagle-import:R0805")
      (libsource (lib "eagle-import") (part "R-EU_R0805"))
    )
    (comp (ref "R53")
      (value "1K")
      (footprint "eagle-import:R0805")
      (libsource (lib "eagle-import") (part "R-EU_R0805"))
    )
    (comp (ref "R54")
      (value "1K")
      (footprint "eagle-import:R0805")
      (libsource (lib "eagle-import") (part "R-EU_R0805"))
    )
    (comp (ref "R55")
      (value "10K")
      (footprint "eagle-import:R0805")
      (libsource (lib "eagle-import") (part "R-EU_R0805"))
    )
    (comp (ref "R56")
      (value "10K")
      (footprint "eagle-import:R0805")
      (libsource (lib "eagle-import") (part "R-EU_R0805"))
    )
  )
  (nets
    (net (code "2") (name "+5V") (class "Default")
      (node (ref "C10") (pin "+") (pinfunction "+_+") (pintype "passive"))
      (node (ref "C13") (pin "2") (pinfunction "2_2") (pintype "passive"))
      (node (ref "C14") (pin "2") (pinfunction "2_2") (pintype "passive"))
      (node (ref "C15") (pin "1") (pinfunction "1_1") (pintype "passive"))
      (node (ref "C4") (pin "2") (pinfunction "2_2") (pintype "passive"))
      (node (ref "C6") (pin "1") (pinfunction "1_1") (pintype "passive"))
      (node (ref "C7") (pin "1") (pinfunction "1_1") (pintype "passive"))
      (node (ref "IC1") (pin "16") (pinfunction "VCC_16") (pintype "power_in"))
      (node (ref "IC2") (pin "16") (pinfunction "VCC_16") (pintype "power_in"))
      (node (ref "ISP1") (pin "2") (pinfunction "VCC_2") (pintype "power_in"))
      (node (ref "J1") (pin "VCC") (pinfunction "4_VCC") (pintype "passive"))
      (node (ref "JP10") (pin "1") (pinfunction "1_1") (pintype "passive"))
      (node (ref "R1") (pin "2") (pinfunction "2_2") (pintype "passive"))
      (node (ref "R2") (pin "2") (pinfunction "2_2") (pintype "passive"))
      (node (ref "R4") (pin "2") (pinfunction "2_2") (pintype "passive"))
      (node (ref "R58") (pin "2") (pinfunction "2_2") (pintype "passive"))
      (node (ref "R6") (pin "2") (pinfunction "2_2") (pintype "passive"))
      (node (ref "R61") (pin "1") (pinfunction "1_1") (pintype "passive"))
      (node (ref "SJ3") (pin "1") (pinfunction "1_1") (pintype "passive"))
      (node (ref "U1") (pin "18") (pinfunction "AVCC_18") (pintype "power_in"))
      (node (ref "U1") (pin "20") (pinfunction "AREF_20") (pintype "power_in"))
      (node (ref "U1") (pin "4") (pinfunction "VCC_4") (pintype "power_in"))
      (node (ref "U2") (pin "14") (pinfunction "VCC_14") (pintype "bidirectional"))
      (node (ref "U3") (pin "1") (pinfunction "SHDWN_1") (pintype "bidirectional"))
      (node (ref "U3") (pin "6") (pinfunction "VDD_6") (pintype "bidirectional"))
      (node (ref "U4") (pin "10") (pinfunction "VLOGIC_10") (pintype "bidirectional"))
      (node (ref "U4") (pin "13") (pinfunction "WP_13") (pintype "bidirectional"))
      (node (ref "U4") (pin "16") (pinfunction "LRDAC_16") (pintype "bidirectional"))
      (node (ref "U4") (pin "9") (pinfunction "VDD_9") (pintype "bidirectional"))
      (node (ref "X3") (pin "1") (pinfunction "S_1") (pintype "passive"))
    )
    (net (code "3") (name "+12V") (class "Default")
      (node (ref "C16") (pin "+") (pinfunction "+_+") (pintype "passive"))
      (node (ref "IC3") (pin "1") (pinfunction "IN_1") (pintype "input"))
      (node (ref "JP10") (pin "2") (pinfunction "2_2") (pintype "passive"))
      (node (ref "Q11") (pin "2") (pinfunction "S_2") (pintype "passive"))
      (node (ref "Q12") (pin "2") (pinfunction "S_2") (pintype "passive"))
      (node (ref "Q13") (pin "2") (pinfunction "S_2") (pintype "passive"))
      (node (ref "Q17") (pin "2") (pinfunction "S_2") (pintype "passive"))
      (node (ref "Q18") (pin "2") (pinfunction "S_2") (pintype "passive"))
      (node (ref "Q19") (pin "2") (pinfunction "S_2") (pintype "passive"))
      (node (ref "Q5") (pin "2") (pinfunction "S_2") (pintype "passive"))
      (node (ref "Q6") (pin "2") (pinfunction "S_2") (pintype "passive"))
      (node (ref "Q7") (pin "2") (pinfunction "S_2") (pintype "passive"))
      (node (ref "R13") (pin "2") (pinfunction "2_2") (pintype "passive"))
      (node (ref "R14") (pin "2") (pinfunction "2_2") (pintype "passive"))
      (node (ref "R15") (pin "2") (pinfunction "2_2") (pintype "passive"))
      (node (ref "R25") (pin "2") (pinfunction "2_2") (pintype "passive"))
      (node (ref "R26") (pin "2") (pinfunction "2_2") (pintype "passive"))
      (node (ref "R27") (pin "2") (pinfunction "2_2") (pintype "passive"))
      (node (ref "R37") (pin "2") (pinfunction "2_2") (pintype "passive"))
      (node (ref "R38") (pin "2") (pinfunction "2_2") (pintype "passive"))
      (node (ref "R39") (pin "2") (pinfunction "2_2") (pintype "passive"))
      (node (ref "SJ1") (pin "2") (pinfunction "2_2") (pintype "passive"))
      (node (ref "SJ2") (pin "3") (pinfunction "3_3") (pintype "passive"))
      (node (ref "X18") (pin "1") (pinfunction "S_1") (pintype "passive"))
      (node (ref "X18") (pin "2") (pinfunction "S_2") (pintype "passive"))
      (node (ref "X19") (pin "1") (pinfunction "S_1") (pintype "passive"))
      (node (ref "X19") (pin "2") (pinfunction "S_2") (pintype "passive"))
      (node (ref "X20") (pin "1") (pinfunction "S_1") (pintype "passive"))
      (node (ref "X20") (pin "2") (pinfunction "S_2") (pintype "passive"))
      (node (ref "X21") (pin "1") (pinfunction "S_1") (pintype "passive"))
      (node (ref "X21") (pin "2") (pinfunction "S_2") (pintype "passive"))
    )
    (net (code "5") (name "A") (class "Default")
      (node (ref "Q20") (pin "3") (pinfunction "D_3") (pintype "bidirectional"))
      (node (ref "X10") (pin "5") (pinfunction "S_5") (pintype "passive"))
      (node (ref "X11") (pin "5") (pinfunction "S_5") (pintype "passive"))
      (node (ref "X12") (pin "5") (pinfunction "S_5") (pintype "passive"))
      (node (ref "X13") (pin "5") (pinfunction "S_5") (pintype "passive"))
      (node (ref "X14") (pin "5") (pinfunction "S_5") (pintype "passive"))
      (node (ref "X6") (pin "5") (pinfunction "S_5") (pintype "passive"))
      (node (ref "X7") (pin "5") (pinfunction "S_5") (pintype "passive"))
      (node (ref "X8") (pin "5") (pinfunction "S_5") (pintype "passive"))
      (node (ref "X9") (pin "5") (pinfunction "S_5") (pintype "passive"))
    )
    (net (code "6") (name "ADSOUND+") (class "Default")
      (node (ref "SJ4") (pin "1") (pinfunction "1_1") (pintype "passive"))
      (node (ref "U3") (pin "5") (pinfunction "OUT+_5") (pintype "bidirectional"))
    )
    (net (code "7") (name "ADSOUND-") (class "Default")
      (node (ref "SJ5") (pin "3") (pinfunction "3_3") (pintype "passive"))
      (node (ref "U3") (pin "8") (pinfunction "OUT-_8") (pintype "bidirectional"))
    )
    (net (code "8") (name "AN1") (class "Default")
      (node (ref "IC1") (pin "7") (pinfunction "QH_7") (pintype "tri_state"))
      (node (ref "R7") (pin "1") (pinfunction "1_1") (pintype "passive"))
    )
    (net (code "9") (name "AN2") (class "Default")
      (node (ref "IC2") (pin "15") (pinfunction "QA_15") (pintype "tri_state"))
      (node (ref "R19") (pin "1") (pinfunction "1_1") (pintype "passive"))
    )
    (net (code "10") (name "AN3") (class "Default")
      (node (ref "IC2") (pin "1") (pinfunction "QB_1") (pintype "tri_state"))
      (node (ref "R31") (pin "1") (pinfunction "1_1") (pintype "passive"))
    )
    (net (code "11") (name "AN4") (class "Default")
      (node (ref "IC2") (pin "2") (pinfunction "QC_2") (pintype "tri_state"))
      (node (ref "R8") (pin "1") (pinfunction "1_1") (pintype "passive"))
    )
    (net (code "12") (name "AN5") (class "Default")
      (node (ref "IC2") (pin "3") (pinfunction "QD_3") (pintype "tri_state"))
      (node (ref "R20") (pin "1") (pinfunction "1_1") (pintype "passive"))
    )
    (net (code "13") (name "AN6") (class "Default")
      (node (ref "IC2") (pin "4") (pinfunction "QE_4") (pintype "tri_state"))
      (node (ref "R32") (pin "1") (pinfunction "1_1") (pintype "passive"))
    )
    (net (code "14") (name "AN7") (class "Default")
      (node (ref "IC2") (pin "5") (pinfunction "QF_5") (pintype "tri_state"))
      (node (ref "R9") (pin "1") (pinfunction "1_1") (pintype "passive"))
    )
    (net (code "15") (name "AN8") (class "Default")
      (node (ref "IC2") (pin "6") (pinfunction "QG_6") (pintype "tri_state"))
      (node (ref "R21") (pin "1") (pinfunction "1_1") (pintype "passive"))
    )
    (net (code "16") (name "AN9") (class "Default")
      (node (ref "IC2") (pin "7") (pinfunction "QH_7") (pintype "tri_state"))
      (node (ref "R33") (pin "1") (pinfunction "1_1") (pintype "passive"))
    )
    (net (code "17") (name "B") (class "Default")
      (node (ref "Q21") (pin "3") (pinfunction "D_3") (pintype "bidirectional"))
      (node (ref "X10") (pin "6") (pinfunction "S_6") (pintype "passive"))
      (node (ref "X11") (pin "6") (pinfunction "S_6") (pintype "passive"))
      (node (ref "X12") (pin "6") (pinfunction "S_6") (pintype "passive"))
      (node (ref "X13") (pin "6") (pinfunction "S_6") (pintype "passive"))
      (node (ref "X14") (pin "6") (pinfunction "S_6") (pintype "passive"))
      (node (ref "X6") (pin "6") (pinfunction "S_6") (pintype "passive"))
      (node (ref "X7") (pin "6") (pinfunction "S_6") (pintype "passive"))
      (node (ref "X8") (pin "6") (pinfunction "S_6") (pintype "passive"))
      (node (ref "X9") (pin "6") (pinfunction "S_6") (pintype "passive"))
    )
    (net (code "18") (name "B_COL_0") (class "Default")
      (node (ref "U1") (pin "32") (pinfunction "PD2_32") (pintype "bidirectional"))
      (node (ref "X1") (pin "4") (pinfunction "S_4") (pintype "passive"))
      (node (ref "X2") (pin "4") (pinfunction "S_4") (pintype "passive"))
    )
    (net (code "19") (name "B_COL_1") (class "Default")
      (node (ref "U1") (pin "1") (pinfunction "PD3_1") (pintype "bidirectional"))
      (node (ref "X1") (pin "5") (pinfunction "S_5") (pintype "passive"))
      (node (ref "X2") (pin "5") (pinfunction "S_5") (pintype "passive"))
    )
    (net (code "20") (name "B_COL_2") (class "Default")
      (node (ref "U1") (pin "2") (pinfunction "PD4_2") (pintype "bidirectional"))
      (node (ref "X1") (pin "6") (pinfunction "S_6") (pintype "passive"))
      (node (ref "X2") (pin "6") (pinfunction "S_6") (pintype "passive"))
    )
    (net (code "21") (name "B_COL_3") (class "Default")
      (node (ref "U1") (pin "9") (pinfunction "PD5_9") (pintype "bidirectional"))
      (node (ref "X4") (pin "4") (pinfunction "S_4") (pintype "passive"))
      (node (ref "X5") (pin "4") (pinfunction "S_4") (pintype "passive"))
    )
    (net (code "22") (name "B_COL_4") (class "Default")
      (node (ref "U1") (pin "10") (pinfunction "PD6_10") (pintype "bidirectional"))
      (node (ref "X4") (pin "5") (pinfunction "S_5") (pintype "passive"))
      (node (ref "X5") (pin "5") (pinfunction "S_5") (pintype "passive"))
    )
    (net (code "23") (name "B_COL_5") (class "Default")
      (node (ref "U1") (pin "11") (pinfunction "PD7_11") (pintype "bidirectional"))
      (node (ref "X4") (pin "6") (pinfunction "S_6") (pintype "passive"))
      (node (ref "X5") (pin "6") (pinfunction "S_6") (pintype "passive"))
    )
    (net (code "24") (name "B_ROW_0") (class "Default")
      (node (ref "U1") (pin "23") (pinfunction "PC0_23") (pintype "bidirectional"))
      (node (ref "X1") (pin "1") (pinfunction "S_1") (pintype "passive"))
      (node (ref "X4") (pin "1") (pinfunction "S_1") (pintype "passive"))
    )
    (net (code "25") (name "B_ROW_1") (class "Default")
      (node (ref "U1") (pin "24") (pinfunction "PC1_24") (pintype "bidirectional"))
      (node (ref "X1") (pin "2") (pinfunction "S_2") (pintype "passive"))
      (node (ref "X4") (pin "2") (pinfunction "S_2") (pintype "passive"))
    )
    (net (code "26") (name "B_ROW_2") (class "Default")
      (node (ref "U1") (pin "25") (pinfunction "PC2_25") (pintype "bidirectional"))
      (node (ref "X1") (pin "3") (pinfunction "S_3") (pintype "passive"))
      (node (ref "X4") (pin "3") (pinfunction "S_3") (pintype "passive"))
    )
    (net (code "27") (name "B_ROW_3") (class "Default")
      (node (ref "U1") (pin "26") (pinfunction "PC3_26") (pintype "bidirectional"))
      (node (ref "X2") (pin "1") (pinfunction "S_1") (pintype "passive"))
      (node (ref "X5") (pin "1") (pinfunction "S_1") (pintype "passive"))
    )
    (net (code "28") (name "B_ROW_4") (class "Default")
      (node (ref "U1") (pin "27") (pinfunction "PC4_27") (pintype "bidirectional"))
      (node (ref "X2") (pin "2") (pinfunction "S_2") (pintype "passive"))
      (node (ref "X5") (pin "2") (pinfunction "S_2") (pintype "passive"))
    )
    (net (code "29") (name "B_ROW_5") (class "Default")
      (node (ref "U1") (pin "28") (pinfunction "PC5_28") (pintype "bidirectional"))
      (node (ref "X2") (pin "3") (pinfunction "S_3") (pintype "passive"))
      (node (ref "X5") (pin "3") (pinfunction "S_3") (pintype "passive"))
    )
    (net (code "30") (name "C") (class "Default")
      (node (ref "Q22") (pin "3") (pinfunction "D_3") (pintype "bidirectional"))
      (node (ref "X10") (pin "7") (pinfunction "S_7") (pintype "passive"))
      (node (ref "X11") (pin "7") (pinfunction "S_7") (pintype "passive"))
      (node (ref "X12") (pin "7") (pinfunction "S_7") (pintype "passive"))
      (node (ref "X13") (pin "7") (pinfunction "S_7") (pintype "passive"))
      (node (ref "X14") (pin "7") (pinfunction "S_7") (pintype "passive"))
      (node (ref "X6") (pin "7") (pinfunction "S_7") (pintype "passive"))
      (node (ref "X7") (pin "7") (pinfunction "S_7") (pintype "passive"))
      (node (ref "X8") (pin "7") (pinfunction "S_7") (pintype "passive"))
      (node (ref "X9") (pin "7") (pinfunction "S_7") (pintype "passive"))
    )
    (net (code "31") (name "D") (class "Default")
      (node (ref "Q23") (pin "3") (pinfunction "D_3") (pintype "bidirectional"))
      (node (ref "X10") (pin "1") (pinfunction "S_1") (pintype "passive"))
      (node (ref "X11") (pin "1") (pinfunction "S_1") (pintype "passive"))
      (node (ref "X12") (pin "1") (pinfunction "S_1") (pintype "passive"))
      (node (ref "X13") (pin "1") (pinfunction "S_1") (pintype "passive"))
      (node (ref "X14") (pin "1") (pinfunction "S_1") (pintype "passive"))
      (node (ref "X6") (pin "1") (pinfunction "S_1") (pintype "passive"))
      (node (ref "X7") (pin "1") (pinfunction "S_1") (pintype "passive"))
      (node (ref "X8") (pin "1") (pinfunction "S_1") (pintype "passive"))
      (node (ref "X9") (pin "1") (pinfunction "S_1") (pintype "passive"))
    )
    (net (code "32") (name "D+") (class "Default")
      (node (ref "JP5") (pin "3") (pinfunction "3_3") (pintype "passive"))
      (node (ref "R58") (pin "1") (pinfunction "1_1") (pintype "passive"))
      (node (ref "R59") (pin "2") (pinfunction "2_2") (pintype "passive"))
      (node (ref "R60") (pin "2") (pinfunction "2_2") (pintype "passive"))
      (node (ref "U$1") (pin "P$3") (pinfunction "D+_P$3") (pintype "bidirectional"))
    )
    (net (code "33") (name "D-") (class "Default")
      (node (ref "JP5") (pin "2") (pinfunction "2_2") (pintype "passive"))
      (node (ref "R61") (pin "2") (pinfunction "2_2") (pintype "passive"))
      (node (ref "R62") (pin "1") (pinfunction "1_1") (pintype "passive"))
      (node (ref "R63") (pin "1") (pinfunction "1_1") (pintype "passive"))
      (node (ref "U$1") (pin "P$2") (pinfunction "D-_P$2") (pintype "bidirectional"))
    )
    (net (code "34") (name "DTR") (class "Default")
      (node (ref "C1") (pin "2") (pinfunction "2_2") (pintype "passive"))
      (node (ref "J1") (pin "DTR") (pinfunction "1_DTR") (pintype "passive"))
    )
    (net (code "35") (name "E") (class "Default")
      (node (ref "Q24") (pin "3") (pinfunction "D_3") (pintype "bidirectional"))
      (node (ref "X10") (pin "2") (pinfunction "S_2") (pintype "passive"))
      (node (ref "X11") (pin "2") (pinfunction "S_2") (pintype "passive"))
      (node (ref "X12") (pin "2") (pinfunction "S_2") (pintype "passive"))
      (node (ref "X13") (pin "2") (pinfunction "S_2") (pintype "passive"))
      (node (ref "X14") (pin "2") (pinfunction "S_2") (pintype "passive"))
      (node (ref "X6") (pin "2") (pinfunction "S_2") (pintype "passive"))
      (node (ref "X7") (pin "2") (pinfunction "S_2") (pintype "passive"))
      (node (ref "X8") (pin "2") (pinfunction "S_2") (pintype "passive"))
      (node (ref "X9") (pin "2") (pinfunction "S_2") (pintype "passive"))
    )
    (net (code "36") (name "F") (class "Default")
      (node (ref "Q25") (pin "3") (pinfunction "D_3") (pintype "bidirectional"))
      (node (ref "X10") (pin "4") (pinfunction "S_4") (pintype "passive"))
      (node (ref "X11") (pin "4") (pinfunction "S_4") (pintype "passive"))
      (node (ref "X12") (pin "4") (pinfunction "S_4") (pintype "passive"))
      (node (ref "X13") (pin "4") (pinfunction "S_4") (pintype "passive"))
      (node (ref "X14") (pin "4") (pinfunction "S_4") (pintype "passive"))
      (node (ref "X6") (pin "4") (pinfunction "S_4") (pintype "passive"))
      (node (ref "X7") (pin "4") (pinfunction "S_4") (pintype "passive"))
      (node (ref "X8") (pin "4") (pinfunction "S_4") (pintype "passive"))
      (node (ref "X9") (pin "4") (pinfunction "S_4") (pintype "passive"))
    )
    (net (code "37") (name "FTDIRX") (class "Default")
      (node (ref "J1") (pin "TXO") (pinfunction "3_TXO") (pintype "passive"))
      (node (ref "JP1") (pin "2") (pinfunction "2_2") (pintype "passive"))
    )
    (net (code "38") (name "FTDITX") (class "Default")
      (node (ref "J1") (pin "RXI") (pinfunction "2_RXI") (pintype "passive"))
      (node (ref "JP2") (pin "2") (pinfunction "2_2") (pintype "passive"))
    )
    (net (code "39") (name "G") (class "Default")
      (node (ref "Q26") (pin "3") (pinfunction "D_3") (pintype "bidirectional"))
      (node (ref "X10") (pin "3") (pinfunction "S_3") (pintype "passive"))
      (node (ref "X11") (pin "3") (pinfunction "S_3") (pintype "passive"))
      (node (ref "X12") (pin "3") (pinfunction "S_3") (pintype "passive"))
      (node (ref "X13") (pin "3") (pinfunction "S_3") (pintype "passive"))
      (node (ref "X14") (pin "3") (pinfunction "S_3") (pintype "passive"))
      (node (ref "X6") (pin "3") (pinfunction "S_3") (pintype "passive"))
      (node (ref "X7") (pin "3") (pinfunction "S_3") (pintype "passive"))
      (node (ref "X8") (pin "3") (pinfunction "S_3") (pintype "passive"))
      (node (ref "X9") (pin "3") (pinfunction "S_3") (pintype "passive"))
    )
    (net (code "40") (name "GND") (class "Default")
      (node (ref "C10") (pin "-") (pinfunction "-_-") (pintype "passive"))
      (node (ref "C11") (pin "2") (pinfunction "2_2") (pintype "passive"))
      (node (ref "C13") (pin "1") (pinfunction "1_1") (pintype "passive"))
      (node (ref "C14") (pin "1") (pinfunction "1_1") (pintype "passive"))
      (node (ref "C15") (pin "2") (pinfunction "2_2") (pintype "passive"))
      (node (ref "C16") (pin "-") (pinfunction "-_-") (pintype "passive"))
      (node (ref "C17") (pin "-") (pinfunction "-_-") (pintype "passive"))
      (node (ref "C2") (pin "1") (pinfunction "1_1") (pintype "passive"))
      (node (ref "C3") (pin "1") (pinfunction "1_1") (pintype "passive"))
      (node (ref "C4") (pin "1") (pinfunction "1_1") (pintype "passive"))
      (node (ref "C5") (pin "1") (pinfunction "1_1") (pintype "passive"))
      (node (ref "C6") (pin "2") (pinfunction "2_2") (pintype "passive"))
      (node (ref "C7") (pin "2") (pinfunction "2_2") (pintype "passive"))
      (node (ref "C9") (pin "1") (pinfunction "1_1") (pintype "passive"))
      (node (ref "D1") (pin "A") (pinfunction "A_A") (pintype "passive"))
      (node (ref "IC1") (pin "8") (pinfunction "GND_8") (pintype "power_in"))
      (node (ref "IC2") (pin "8") (pinfunction "GND_8") (pintype "power_in"))
      (node (ref "IC3") (pin "3") (pinfunction "GND_3") (pintype "power_in"))
      (node (ref "IC3") (pin "6") (pinfunction "GND_6") (pintype "power_in"))
      (node (ref "ISP1") (pin "6") (pinfunction "GND_6") (pintype "power_in"))
      (node (ref "J1") (pin "CTS") (pinfunction "5_CTS") (pintype "passive"))
      (node (ref "J1") (pin "GND") (pinfunction "6_GND") (pintype "passive"))
      (node (ref "JP10") (pin "3") (pinfunction "3_3") (pintype "passive"))
      (node (ref "JP5") (pin "5") (pinfunction "5_5") (pintype "passive"))
      (node (ref "JP6") (pin "1") (pinfunction "1_1") (pintype "passive"))
      (node (ref "JP6") (pin "2") (pinfunction "2_2") (pintype "passive"))
      (node (ref "JP6") (pin "3") (pinfunction "3_3") (pintype "passive"))
      (node (ref "JP6") (pin "4") (pinfunction "4_4") (pintype "passive"))
      (node (ref "Q10") (pin "2") (pinfunction "S_2") (pintype "bidirectional"))
      (node (ref "Q14") (pin "2") (pinfunction "S_2") (pintype "bidirectional"))
      (node (ref "Q15") (pin "2") (pinfunction "S_2") (pintype "bidirectional"))
      (node (ref "Q16") (pin "2") (pinfunction "S_2") (pintype "bidirectional"))
      (node (ref "Q2") (pin "2") (pinfunction "S_2") (pintype "bidirectional"))
      (node (ref "Q20") (pin "2") (pinfunction "S_2") (pintype "bidirectional"))
      (node (ref "Q21") (pin "2") (pinfunction "S_2") (pintype "bidirectional"))
      (node (ref "Q22") (pin "2") (pinfunction "S_2") (pintype "bidirectional"))
      (node (ref "Q23") (pin "2") (pinfunction "S_2") (pintype "bidirectional"))
      (node (ref "Q24") (pin "2") (pinfunction "S_2") (pintype "bidirectional"))
      (node (ref "Q25") (pin "2") (pinfunction "S_2") (pintype "bidirectional"))
      (node (ref "Q26") (pin "2") (pinfunction "S_2") (pintype "bidirectional"))
      (node (ref "Q3") (pin "2") (pinfunction "S_2") (pintype "bidirectional"))
      (node (ref "Q4") (pin "2") (pinfunction "S_2") (pintype "bidirectional"))
      (node (ref "Q8") (pin "2") (pinfunction "S_2") (pintype "bidirectional"))
      (node (ref "Q9") (pin "2") (pinfunction "S_2") (pintype "bidirectional"))
      (node (ref "R10") (pin "1") (pinfunction "1_1") (pintype "passive"))
      (node (ref "R11") (pin "1") (pinfunction "1_1") (pintype "passive"))
      (node (ref "R12") (pin "1") (pinfunction "1_1") (pintype "passive"))
      (node (ref "R16") (pin "1") (pinfunction "1_1") (pintype "passive"))
      (node (ref "R17") (pin "1") (pinfunction "1_1") (pintype "passive"))
      (node (ref "R18") (pin "1") (pinfunction "1_1") (pintype "passive"))
      (node (ref "R22") (pin "1") (pinfunction "1_1") (pintype "passive"))
      (node (ref "R23") (pin "1") (pinfunction "1_1") (pintype "passive"))
      (node (ref "R24") (pin "1") (pinfunction "1_1") (pintype "passive"))
      (node (ref "R28") (pin "1") (pinfunction "1_1") (pintype "passive"))
      (node (ref "R29") (pin "1") (pinfunction "1_1") (pintype "passive"))
      (node (ref "R3") (pin "1") (pinfunction "1_1") (pintype "passive"))
      (node (ref "R30") (pin "1") (pinfunction "1_1") (pintype "passive"))
      (node (ref "R34") (pin "1") (pinfunction "1_1") (pintype "passive"))
      (node (ref "R35") (pin "1") (pinfunction "1_1") (pintype "passive"))
      (node (ref "R36") (pin "1") (pinfunction "1_1") (pintype "passive"))
      (node (ref "R40") (pin "1") (pinfunction "1_1") (pintype "passive"))
      (node (ref "R41") (pin "1") (pinfunction "1_1") (pintype "passive"))
      (node (ref "R42") (pin "1") (pinfunction "1_1") (pintype "passive"))
      (node (ref "R48") (pin "1") (pinfunction "1_1") (pintype "passive"))
      (node (ref "R49") (pin "1") (pinfunction "1_1") (pintype "passive"))
      (node (ref "R50") (pin "1") (pinfunction "1_1") (pintype "passive"))
      (node (ref "R51") (pin "1") (pinfunction "1_1") (pintype "passive"))
      (node (ref "R52") (pin "1") (pinfunction "1_1") (pintype "passive"))
      (node (ref "R55") (pin "1") (pinfunction "1_1") (pintype "passive"))
      (node (ref "R56") (pin "1") (pinfunction "1_1") (pintype "passive"))
      (node (ref "R57") (pin "1") (pinfunction "1_1") (pintype "passive"))
      (node (ref "R59") (pin "1") (pinfunction "1_1") (pintype "passive"))
      (node (ref "R62") (pin "2") (pinfunction "2_2") (pintype "passive"))
      (node (ref "SJ2") (pin "1") (pinfunction "1_1") (pintype "passive"))
      (node (ref "SJ5") (pin "1") (pinfunction "1_1") (pintype "passive"))
      (node (ref "SW1") (pin "1") (pinfunction "A1_1") (pintype "bidirectional"))
      (node (ref "U$1") (pin "P$5") (pinfunction "GND_P$5") (pintype "bidirectional"))
      (node (ref "U$1") (pin "P$6") (pinfunction "GND_P$6") (pintype "bidirectional"))
      (node (ref "U$1") (pin "P$8") (pinfunction "GND_P$8") (pintype "bidirectional"))
      (node (ref "U1") (pin "21") (pinfunction "GND_21") (pintype "power_in"))
      (node (ref "U1") (pin "5") (pinfunction "GND_5") (pintype "power_in"))
      (node (ref "U2") (pin "10") (pinfunction "GND_10") (pintype "bidirectional"))
      (node (ref "U2") (pin "11") (pinfunction "GND_11") (pintype "bidirectional"))
      (node (ref "U2") (pin "12") (pinfunction "GND_12") (pintype "bidirectional"))
      (node (ref "U2") (pin "3") (pinfunction "GND_3") (pintype "bidirectional"))
      (node (ref "U2") (pin "4") (pinfunction "GND_4") (pintype "bidirectional"))
      (node (ref "U2") (pin "5") (pinfunction "GND_5") (pintype "bidirectional"))
      (node (ref "U2") (pin "6") (pinfunction "IN-_6") (pintype "bidirectional"))
      (node (ref "U2") (pin "7") (pinfunction "GND_7") (pintype "bidirectional"))
      (node (ref "U3") (pin "7") (pinfunction "GND_7") (pintype "bidirectional"))
      (node (ref "U4") (pin "1") (pinfunction "GND_1") (pintype "power_in"))
      (node (ref "U4") (pin "15") (pinfunction "INDEP_15") (pintype "bidirectional"))
      (node (ref "U4") (pin "17") (pinfunction "VSS_17") (pintype "power_in"))
      (node (ref "U4") (pin "5") (pinfunction "VSS_5") (pintype "power_in"))
      (node (ref "U4") (pin "7") (pinfunction "RESET_7") (pintype "bidirectional"))
      (node (ref "U4") (pin "8") (pinfunction "DIS_8") (pintype "bidirectional"))
      (node (ref "X22") (pin "1") (pinfunction "S_1") (pintype "passive"))
      (node (ref "X22") (pin "2") (pinfunction "S_2") (pintype "passive"))
      (node (ref "X22") (pin "3") (pinfunction "S_3") (pintype "passive"))
      (node (ref "X23") (pin "1") (pinfunction "S_1") (pintype "passive"))
      (node (ref "X23") (pin "2") (pinfunction "S_2") (pintype "passive"))
      (node (ref "X23") (pin "3") (pinfunction "S_3") (pintype "passive"))
      (node (ref "X24") (pin "1") (pinfunction "S_1") (pintype "passive"))
      (node (ref "X24") (pin "2") (pinfunction "S_2") (pintype "passive"))
      (node (ref "X24") (pin "3") (pinfunction "S_3") (pintype "passive"))
      (node (ref "X25") (pin "1") (pinfunction "S_1") (pintype "passive"))
      (node (ref "X25") (pin "2") (pinfunction "S_2") (pintype "passive"))
      (node (ref "X25") (pin "3") (pinfunction "S_3") (pintype "passive"))
      (node (ref "X3") (pin "7") (pinfunction "S_7") (pintype "passive"))
    )
    (net (code "41") (name "LED_B") (class "Default")
      (node (ref "IC1") (pin "10") (pinfunction "SCL_10") (pintype "input"))
      (node (ref "IC2") (pin "10") (pinfunction "SCL_10") (pintype "input"))
      (node (ref "R2") (pin "1") (pinfunction "1_1") (pintype "passive"))
      (node (ref "U1") (pin "14") (pinfunction "PB2_14") (pintype "bidirectional"))
      (node (ref "X3") (pin "5") (pinfunction "S_5") (pintype "passive"))
    )
    (net (code "42") (name "LED_D_OUT") (class "Default")
      (node (ref "IC2") (pin "9") (pinfunction "QH*_9") (pintype "tri_state"))
      (node (ref "X3") (pin "2") (pinfunction "S_2") (pintype "passive"))
    )
    (net (code "43") (name "LED_L") (class "Default")
      (node (ref "IC1") (pin "12") (pinfunction "RCK_12") (pintype "input"))
      (node (ref "IC2") (pin "12") (pinfunction "RCK_12") (pintype "input"))
      (node (ref "R1") (pin "1") (pinfunction "1_1") (pintype "passive"))
      (node (ref "U1") (pin "12") (pinfunction "PB0_12") (pintype "bidirectional"))
      (node (ref "X3") (pin "4") (pinfunction "S_4") (pintype "passive"))
    )
    (net (code "44") (name "LED_O") (class "Default")
      (node (ref "IC1") (pin "13") (pinfunction "G_13") (pintype "input"))
      (node (ref "IC2") (pin "13") (pinfunction "G_13") (pintype "input"))
      (node (ref "R3") (pin "2") (pinfunction "2_2") (pintype "passive"))
      (node (ref "U1") (pin "19") (pinfunction "PE2_19") (pintype "bidirectional"))
      (node (ref "X3") (pin "6") (pinfunction "S_6") (pintype "passive"))
    )
    (net (code "45") (name "LMSOUND") (class "Default")
      (node (ref "C12") (pin "-") (pinfunction "-_-") (pintype "passive"))
      (node (ref "SJ4") (pin "3") (pinfunction "3_3") (pintype "passive"))
    )
    (net (code "46") (name "MISO") (class "Default")
      (node (ref "ISP1") (pin "1") (pinfunction "MISO_1") (pintype "input"))
      (node (ref "U1") (pin "16") (pinfunction "PB4_16") (pintype "bidirectional"))
      (node (ref "U4") (pin "14") (pinfunction "SDO_AD1_14") (pintype "bidirectional"))
    )
    (net (code "47") (name "MOSI") (class "Default")
      (node (ref "IC1") (pin "14") (pinfunction "SER_14") (pintype "input"))
      (node (ref "ISP1") (pin "4") (pinfunction "MOSI_4") (pintype "output"))
      (node (ref "U1") (pin "15") (pinfunction "PB3_15") (pintype "bidirectional"))
      (node (ref "U4") (pin "12") (pinfunction "SDI_SDA_12") (pintype "bidirectional"))
    )
    (net (code "48") (name "Net-(IC1A-QH*)") (class "Default")
      (node (ref "IC1") (pin "9") (pinfunction "QH*_9") (pintype "tri_state"))
      (node (ref "IC2") (pin "14") (pinfunction "SER_14") (pintype "input"))
    )
    (net (code "49") (name "Net-(IC3-EN)") (class "Default")
      (node (ref "IC3") (pin "5") (pinfunction "EN_5") (pintype "input"))
      (node (ref "SJ2") (pin "2") (pinfunction "2_2") (pintype "passive"))
    )
    (net (code "50") (name "Net-(IC3-FB)") (class "Default")
      (node (ref "C17") (pin "+") (pinfunction "+_+") (pintype "passive"))
      (node (ref "IC3") (pin "4") (pinfunction "FB_4") (pintype "input"))
      (node (ref "L1") (pin "P$2") (pinfunction "2_P$2") (pintype "passive"))
      (node (ref "SJ3") (pin "2") (pinfunction "2_2") (pintype "passive"))
    )
    (net (code "51") (name "Net-(IC3-OUT)") (class "Default")
      (node (ref "D1") (pin "C") (pinfunction "C_C") (pintype "passive"))
      (node (ref "IC3") (pin "2") (pinfunction "OUT_2") (pintype "output"))
      (node (ref "L1") (pin "P$1") (pinfunction "1_P$1") (pintype "passive"))
    )
    (net (code "52") (name "Net-(Q2-D)") (class "Default")
      (node (ref "Q2") (pin "3") (pinfunction "D_3") (pintype "bidirectional"))
      (node (ref "Q5") (pin "1") (pinfunction "G_1") (pintype "passive"))
      (node (ref "R13") (pin "1") (pinfunction "1_1") (pintype "passive"))
    )
    (net (code "53") (name "Net-(Q2-G)") (class "Default")
      (node (ref "Q2") (pin "1") (pinfunction "G_1") (pintype "bidirectional"))
      (node (ref "R10") (pin "2") (pinfunction "2_2") (pintype "passive"))
      (node (ref "R7") (pin "2") (pinfunction "2_2") (pintype "passive"))
    )
    (net (code "54") (name "Net-(Q3-D)") (class "Default")
      (node (ref "Q3") (pin "3") (pinfunction "D_3") (pintype "bidirectional"))
      (node (ref "Q6") (pin "1") (pinfunction "G_1") (pintype "passive"))
      (node (ref "R14") (pin "1") (pinfunction "1_1") (pintype "passive"))
    )
    (net (code "55") (name "Net-(Q3-G)") (class "Default")
      (node (ref "Q3") (pin "1") (pinfunction "G_1") (pintype "bidirectional"))
      (node (ref "R11") (pin "2") (pinfunction "2_2") (pintype "passive"))
      (node (ref "R8") (pin "2") (pinfunction "2_2") (pintype "passive"))
    )
    (net (code "56") (name "Net-(Q4-D)") (class "Default")
      (node (ref "Q4") (pin "3") (pinfunction "D_3") (pintype "bidirectional"))
      (node (ref "Q7") (pin "1") (pinfunction "G_1") (pintype "passive"))
      (node (ref "R15") (pin "1") (pinfunction "1_1") (pintype "passive"))
    )
    (net (code "57") (name "Net-(Q4-G)") (class "Default")
      (node (ref "Q4") (pin "1") (pinfunction "G_1") (pintype "bidirectional"))
      (node (ref "R12") (pin "2") (pinfunction "2_2") (pintype "passive"))
      (node (ref "R9") (pin "2") (pinfunction "2_2") (pintype "passive"))
    )
    (net (code "58") (name "Net-(Q8-G)") (class "Default")
      (node (ref "Q8") (pin "1") (pinfunction "G_1") (pintype "bidirectional"))
      (node (ref "R19") (pin "2") (pinfunction "2_2") (pintype "passive"))
      (node (ref "R22") (pin "2") (pinfunction "2_2") (pintype "passive"))
    )
    (net (code "59") (name "Net-(Q9-G)") (class "Default")
      (node (ref "Q9") (pin "1") (pinfunction "G_1") (pintype "bidirectional"))
      (node (ref "R20") (pin "2") (pinfunction "2_2") (pintype "passive"))
      (node (ref "R23") (pin "2") (pinfunction "2_2") (pintype "passive"))
    )
    (net (code "60") (name "Net-(Q10-D)") (class "Default")
      (node (ref "Q10") (pin "3") (pinfunction "D_3") (pintype "bidirectional"))
      (node (ref "Q13") (pin "1") (pinfunction "G_1") (pintype "passive"))
      (node (ref "R27") (pin "1") (pinfunction "1_1") (pintype "passive"))
    )
    (net (code "61") (name "Net-(Q10-G)") (class "Default")
      (node (ref "Q10") (pin "1") (pinfunction "G_1") (pintype "bidirectional"))
      (node (ref "R21") (pin "2") (pinfunction "2_2") (pintype "passive"))
      (node (ref "R24") (pin "2") (pinfunction "2_2") (pintype "passive"))
    )
    (net (code "62") (name "Net-(Q11-G)") (class "Default")
      (node (ref "Q11") (pin "1") (pinfunction "G_1") (pintype "passive"))
      (node (ref "Q8") (pin "3") (pinfunction "D_3") (pintype "bidirectional"))
      (node (ref "R25") (pin "1") (pinfunction "1_1") (pintype "passive"))
    )
    (net (code "63") (name "Net-(Q12-G)") (class "Default")
      (node (ref "Q12") (pin "1") (pinfunction "G_1") (pintype "passive"))
      (node (ref "Q9") (pin "3") (pinfunction "D_3") (pintype "bidirectional"))
      (node (ref "R26") (pin "1") (pinfunction "1_1") (pintype "passive"))
    )
    (net (code "64") (name "Net-(Q14-D)") (class "Default")
      (node (ref "Q14") (pin "3") (pinfunction "D_3") (pintype "bidirectional"))
      (node (ref "Q17") (pin "1") (pinfunction "G_1") (pintype "passive"))
      (node (ref "R37") (pin "1") (pinfunction "1_1") (pintype "passive"))
    )
    (net (code "65") (name "Net-(Q14-G)") (class "Default")
      (node (ref "Q14") (pin "1") (pinfunction "G_1") (pintype "bidirectional"))
      (node (ref "R31") (pin "2") (pinfunction "2_2") (pintype "passive"))
      (node (ref "R34") (pin "2") (pinfunction "2_2") (pintype "passive"))
    )
    (net (code "66") (name "Net-(Q15-D)") (class "Default")
      (node (ref "Q15") (pin "3") (pinfunction "D_3") (pintype "bidirectional"))
      (node (ref "Q18") (pin "1") (pinfunction "G_1") (pintype "passive"))
      (node (ref "R38") (pin "1") (pinfunction "1_1") (pintype "passive"))
    )
    (net (code "67") (name "Net-(Q15-G)") (class "Default")
      (node (ref "Q15") (pin "1") (pinfunction "G_1") (pintype "bidirectional"))
      (node (ref "R32") (pin "2") (pinfunction "2_2") (pintype "passive"))
      (node (ref "R35") (pin "2") (pinfunction "2_2") (pintype "passive"))
    )
    (net (code "68") (name "Net-(Q16-D)") (class "Default")
      (node (ref "Q16") (pin "3") (pinfunction "D_3") (pintype "bidirectional"))
      (node (ref "Q19") (pin "1") (pinfunction "G_1") (pintype "passive"))
      (node (ref "R39") (pin "1") (pinfunction "1_1") (pintype "passive"))
    )
    (net (code "69") (name "Net-(Q16-G)") (class "Default")
      (node (ref "Q16") (pin "1") (pinfunction "G_1") (pintype "bidirectional"))
      (node (ref "R33") (pin "2") (pinfunction "2_2") (pintype "passive"))
      (node (ref "R36") (pin "2") (pinfunction "2_2") (pintype "passive"))
    )
    (net (code "70") (name "Net-(Q20-G)") (class "Default")
      (node (ref "Q20") (pin "1") (pinfunction "G_1") (pintype "bidirectional"))
      (node (ref "R43") (pin "2") (pinfunction "2_2") (pintype "passive"))
      (node (ref "R48") (pin "2") (pinfunction "2_2") (pintype "passive"))
    )
    (net (code "71") (name "Net-(Q21-G)") (class "Default")
      (node (ref "Q21") (pin "1") (pinfunction "G_1") (pintype "bidirectional"))
      (node (ref "R44") (pin "2") (pinfunction "2_2") (pintype "passive"))
      (node (ref "R49") (pin "2") (pinfunction "2_2") (pintype "passive"))
    )
    (net (code "72") (name "Net-(Q22-G)") (class "Default")
      (node (ref "Q22") (pin "1") (pinfunction "G_1") (pintype "bidirectional"))
      (node (ref "R45") (pin "2") (pinfunction "2_2") (pintype "passive"))
      (node (ref "R50") (pin "2") (pinfunction "2_2") (pintype "passive"))
    )
    (net (code "73") (name "Net-(Q23-G)") (class "Default")
      (node (ref "Q23") (pin "1") (pinfunction "G_1") (pintype "bidirectional"))
      (node (ref "R46") (pin "2") (pinfunction "2_2") (pintype "passive"))
      (node (ref "R51") (pin "2") (pinfunction "2_2") (pintype "passive"))
    )
    (net (code "74") (name "Net-(Q24-G)") (class "Default")
      (node (ref "Q24") (pin "1") (pinfunction "G_1") (pintype "bidirectional"))
      (node (ref "R47") (pin "2") (pinfunction "2_2") (pintype "passive"))
      (node (ref "R52") (pin "2") (pinfunction "2_2") (pintype "passive"))
    )
    (net (code "75") (name "Net-(Q25-G)") (class "Default")
      (node (ref "Q25") (pin "1") (pinfunction "G_1") (pintype "bidirectional"))
      (node (ref "R53") (pin "2") (pinfunction "2_2") (pintype "passive"))
      (node (ref "R55") (pin "2") (pinfunction "2_2") (pintype "passive"))
    )
    (net (code "76") (name "Net-(Q26-G)") (class "Default")
      (node (ref "Q26") (pin "1") (pinfunction "G_1") (pintype "bidirectional"))
      (node (ref "R54") (pin "2") (pinfunction "2_2") (pintype "passive"))
      (node (ref "R56") (pin "2") (pinfunction "2_2") (pintype "passive"))
    )
    (net (code "77") (name "Net-(U$1-+5)") (class "Default")
      (node (ref "JP5") (pin "1") (pinfunction "1_1") (pintype "passive"))
      (node (ref "SJ1") (pin "1") (pinfunction "1_1") (pintype "passive"))
      (node (ref "U$1") (pin "P$1") (pinfunction "+5_P$1") (pintype "bidirectional"))
    )
    (net (code "78") (name "Net-(U$1-ID)") (class "Default")
      (node (ref "JP5") (pin "4") (pinfunction "4_4") (pintype "passive"))
      (node (ref "U$1") (pin "P$4") (pinfunction "ID_P$4") (pintype "bidirectional"))
    )
    (net (code "79") (name "Net-(U1-PB6{slash}XTAL1)") (class "Default")
      (node (ref "C2") (pin "2") (pinfunction "2_2") (pintype "passive"))
      (node (ref "Q1") (pin "1") (pinfunction "1_1") (pintype "passive"))
      (node (ref "U1") (pin "7") (pinfunction "PB6/XTAL1_7") (pintype "bidirectional"))
    )
    (net (code "80") (name "Net-(U1-PB7{slash}XTAL2)") (class "Default")
      (node (ref "C3") (pin "2") (pinfunction "2_2") (pintype "passive"))
      (node (ref "Q1") (pin "2") (pinfunction "2_2") (pintype "passive"))
      (node (ref "U1") (pin "8") (pinfunction "PB7/XTAL2_8") (pintype "bidirectional"))
    )
    (net (code "81") (name "Net-(U2-BYPASS)") (class "Default")
      (node (ref "C11") (pin "1") (pinfunction "1_1") (pintype "passive"))
      (node (ref "U2") (pin "1") (pinfunction "BYPASS_1") (pintype "bidirectional"))
    )
    (net (code "82") (name "Net-(U2-OUT)") (class "Default")
      (node (ref "C12") (pin "+") (pinfunction "+_+") (pintype "passive"))
      (node (ref "U2") (pin "8") (pinfunction "OUT_8") (pintype "bidirectional"))
    )
    (net (code "83") (name "Net-(U3-IN+)") (class "Default")
      (node (ref "C8") (pin "2") (pinfunction "2_2") (pintype "passive"))
      (node (ref "U3") (pin "3") (pinfunction "IN+_3") (pintype "bidirectional"))
    )
    (net (code "84") (name "Net-(U3-IN-)") (class "Default")
      (node (ref "C9") (pin "2") (pinfunction "2_2") (pintype "passive"))
      (node (ref "U3") (pin "4") (pinfunction "IN-_4") (pintype "bidirectional"))
    )
    (net (code "85") (name "Net-(U4-B)") (class "Default")
      (node (ref "R57") (pin "2") (pinfunction "2_2") (pintype "passive"))
      (node (ref "U4") (pin "4") (pinfunction "B_4") (pintype "bidirectional"))
    )
    (net (code "86") (name "Net-(X15B-KL)") (class "Default")
      (node (ref "X15") (pin "2") (pinfunction "KL_2") (pintype "passive"))
      (node (ref "X16") (pin "1") (pinfunction "KL_1") (pintype "passive"))
    )
    (net (code "87") (name "RX") (class "Default")
      (node (ref "JP1") (pin "3") (pinfunction "3_3") (pintype "passive"))
      (node (ref "JP2") (pin "1") (pinfunction "1_1") (pintype "passive"))
      (node (ref "U1") (pin "30") (pinfunction "PD0_30") (pintype "bidirectional"))
    )
    (net (code "88") (name "SCK") (class "Default")
      (node (ref "IC1") (pin "11") (pinfunction "SCK_11") (pintype "input"))
      (node (ref "IC2") (pin "11") (pinfunction "SCK_11") (pintype "input"))
      (node (ref "ISP1") (pin "3") (pinfunction "SCK_3") (pintype "output"))
      (node (ref "U1") (pin "17") (pinfunction "PB5_17") (pintype "bidirectional"))
      (node (ref "U4") (pin "11") (pinfunction "SCLK_SCL_11") (pintype "bidirectional"))
      (node (ref "X3") (pin "3") (pinfunction "S_3") (pintype "passive"))
    )
    (net (code "89") (name "SCORE0_1") (class "Default")
      (node (ref "Q5") (pin "3") (pinfunction "D_3") (pintype "passive"))
      (node (ref "R16") (pin "2") (pinfunction "2_2") (pintype "passive"))
      (node (ref "X6") (pin "8") (pinfunction "S_8") (pintype "passive"))
    )
    (net (code "90") (name "SCORE0_10") (class "Default")
      (node (ref "Q11") (pin "3") (pinfunction "D_3") (pintype "passive"))
      (node (ref "R28") (pin "2") (pinfunction "2_2") (pintype "passive"))
      (node (ref "X7") (pin "8") (pinfunction "S_8") (pintype "passive"))
    )
    (net (code "91") (name "SCORE0_100") (class "Default")
      (node (ref "Q17") (pin "3") (pinfunction "D_3") (pintype "passive"))
      (node (ref "R40") (pin "2") (pinfunction "2_2") (pintype "passive"))
      (node (ref "X8") (pin "8") (pinfunction "S_8") (pintype "passive"))
    )
    (net (code "92") (name "SCORE1_1") (class "Default")
      (node (ref "Q6") (pin "3") (pinfunction "D_3") (pintype "passive"))
      (node (ref "R17") (pin "2") (pinfunction "2_2") (pintype "passive"))
      (node (ref "X9") (pin "8") (pinfunction "S_8") (pintype "passive"))
    )
    (net (code "93") (name "SCORE1_10") (class "Default")
      (node (ref "Q12") (pin "3") (pinfunction "D_3") (pintype "passive"))
      (node (ref "R29") (pin "2") (pinfunction "2_2") (pintype "passive"))
      (node (ref "X10") (pin "8") (pinfunction "S_8") (pintype "passive"))
    )
    (net (code "94") (name "SCORE1_100") (class "Default")
      (node (ref "Q18") (pin "3") (pinfunction "D_3") (pintype "passive"))
      (node (ref "R41") (pin "2") (pinfunction "2_2") (pintype "passive"))
      (node (ref "X11") (pin "8") (pinfunction "S_8") (pintype "passive"))
    )
    (net (code "95") (name "SCORE2_1") (class "Default")
      (node (ref "Q7") (pin "3") (pinfunction "D_3") (pintype "passive"))
      (node (ref "R18") (pin "2") (pinfunction "2_2") (pintype "passive"))
      (node (ref "X12") (pin "8") (pinfunction "S_8") (pintype "passive"))
    )
    (net (code "96") (name "SCORE2_10") (class "Default")
      (node (ref "Q13") (pin "3") (pinfunction "D_3") (pintype "passive"))
      (node (ref "R30") (pin "2") (pinfunction "2_2") (pintype "passive"))
      (node (ref "X13") (pin "8") (pinfunction "S_8") (pintype "passive"))
    )
    (net (code "97") (name "SCORE2_100") (class "Default")
      (node (ref "Q19") (pin "3") (pinfunction "D_3") (pintype "passive"))
      (node (ref "R42") (pin "2") (pinfunction "2_2") (pintype "passive"))
      (node (ref "X14") (pin "8") (pinfunction "S_8") (pintype "passive"))
    )
    (net (code "98") (name "SIGA") (class "Default")
      (node (ref "IC1") (pin "15") (pinfunction "QA_15") (pintype "tri_state"))
      (node (ref "R43") (pin "1") (pinfunction "1_1") (pintype "passive"))
    )
    (net (code "99") (name "SIGB") (class "Default")
      (node (ref "IC1") (pin "1") (pinfunction "QB_1") (pintype "tri_state"))
      (node (ref "R44") (pin "1") (pinfunction "1_1") (pintype "passive"))
    )
    (net (code "100") (name "SIGC") (class "Default")
      (node (ref "IC1") (pin "2") (pinfunction "QC_2") (pintype "tri_state"))
      (node (ref "R45") (pin "1") (pinfunction "1_1") (pintype "passive"))
    )
    (net (code "101") (name "SIGD") (class "Default")
      (node (ref "IC1") (pin "3") (pinfunction "QD_3") (pintype "tri_state"))
      (node (ref "R46") (pin "1") (pinfunction "1_1") (pintype "passive"))
    )
    (net (code "102") (name "SIGE") (class "Default")
      (node (ref "IC1") (pin "4") (pinfunction "QE_4") (pintype "tri_state"))
      (node (ref "R47") (pin "1") (pinfunction "1_1") (pintype "passive"))
    )
    (net (code "103") (name "SIGF") (class "Default")
      (node (ref "IC1") (pin "5") (pinfunction "QF_5") (pintype "tri_state"))
      (node (ref "R53") (pin "1") (pinfunction "1_1") (pintype "passive"))
    )
    (net (code "104") (name "SIGG") (class "Default")
      (node (ref "IC1") (pin "6") (pinfunction "QG_6") (pintype "tri_state"))
      (node (ref "R54") (pin "1") (pinfunction "1_1") (pintype "passive"))
    )
    (net (code "105") (name "SOUND+") (class "Default")
      (node (ref "SJ4") (pin "2") (pinfunction "2_2") (pintype "passive"))
      (node (ref "X15") (pin "1") (pinfunction "KL_1") (pintype "passive"))
    )
    (net (code "106") (name "SOUND-") (class "Default")
      (node (ref "SJ5") (pin "2") (pinfunction "2_2") (pintype "passive"))
      (node (ref "X16") (pin "2") (pinfunction "KL_2") (pintype "passive"))
    )
    (net (code "107") (name "SOUNDOUT") (class "Default")
      (node (ref "SJ6") (pin "2") (pinfunction "2_2") (pintype "passive"))
      (node (ref "U1") (pin "13") (pinfunction "PB1_13") (pintype "bidirectional"))
      (node (ref "U4") (pin "2") (pinfunction "A_2") (pintype "bidirectional"))
    )
    (net (code "108") (name "SOUND_ATND") (class "Default")
      (node (ref "C8") (pin "1") (pinfunction "1_1") (pintype "passive"))
      (node (ref "SJ6") (pin "1") (pinfunction "1_1") (pintype "passive"))
      (node (ref "U2") (pin "2") (pinfunction "IN+_2") (pintype "bidirectional"))
      (node (ref "U4") (pin "3") (pinfunction "W_3") (pintype "bidirectional"))
    )
    (net (code "109") (name "SOUND_CS") (class "Default")
      (node (ref "R4") (pin "1") (pinfunction "1_1") (pintype "passive"))
      (node (ref "U1") (pin "22") (pinfunction "PE3_22") (pintype "bidirectional"))
      (node (ref "U4") (pin "6") (pinfunction "SY_AD0_6") (pintype "bidirectional"))
    )
    (net (code "110") (name "TX") (class "Default")
      (node (ref "JP1") (pin "1") (pinfunction "1_1") (pintype "passive"))
      (node (ref "JP2") (pin "3") (pinfunction "3_3") (pintype "passive"))
      (node (ref "U1") (pin "31") (pinfunction "PD1_31") (pintype "bidirectional"))
    )
    (net (code "111") (name "UCD+") (class "Default")
      (node (ref "R60") (pin "1") (pinfunction "1_1") (pintype "passive"))
      (node (ref "U1") (pin "3") (pinfunction "PE0_3") (pintype "bidirectional"))
    )
    (net (code "112") (name "UCD-") (class "Default")
      (node (ref "R63") (pin "2") (pinfunction "2_2") (pintype "passive"))
      (node (ref "U1") (pin "6") (pinfunction "PE1_6") (pintype "bidirectional"))
    )
    (net (code "113") (name "UC_RESET") (class "Default")
      (node (ref "C1") (pin "1") (pinfunction "1_1") (pintype "passive"))
      (node (ref "C5") (pin "2") (pinfunction "2_2") (pintype "passive"))
      (node (ref "ISP1") (pin "5") (pinfunction "RST_5") (pintype "output"))
      (node (ref "R6") (pin "1") (pinfunction "1_1") (pintype "passive"))
      (node (ref "SW1") (pin "3") (pinfunction "B1_3") (pintype "bidirectional"))
      (node (ref "U1") (pin "29") (pinfunction "PC6/RESET_29") (pintype "bidirectional"))
    )
    (net (code "114") (name "unconnected-(SW1-A2-Pad2)") (class "Default")
      (node (ref "SW1") (pin "2") (pinfunction "A2_2") (pintype "bidirectional"))
    )
    (net (code "115") (name "unconnected-(SW1-B2-Pad4)") (class "Default")
      (node (ref "SW1") (pin "4") (pinfunction "B2_4") (pintype "bidirectional"))
    )
  )
)
